# All-in-one_Starter_Kit_for_Pico_2V_1_0_1.net
KiCad netlist of a schematic drawn in EAGLE
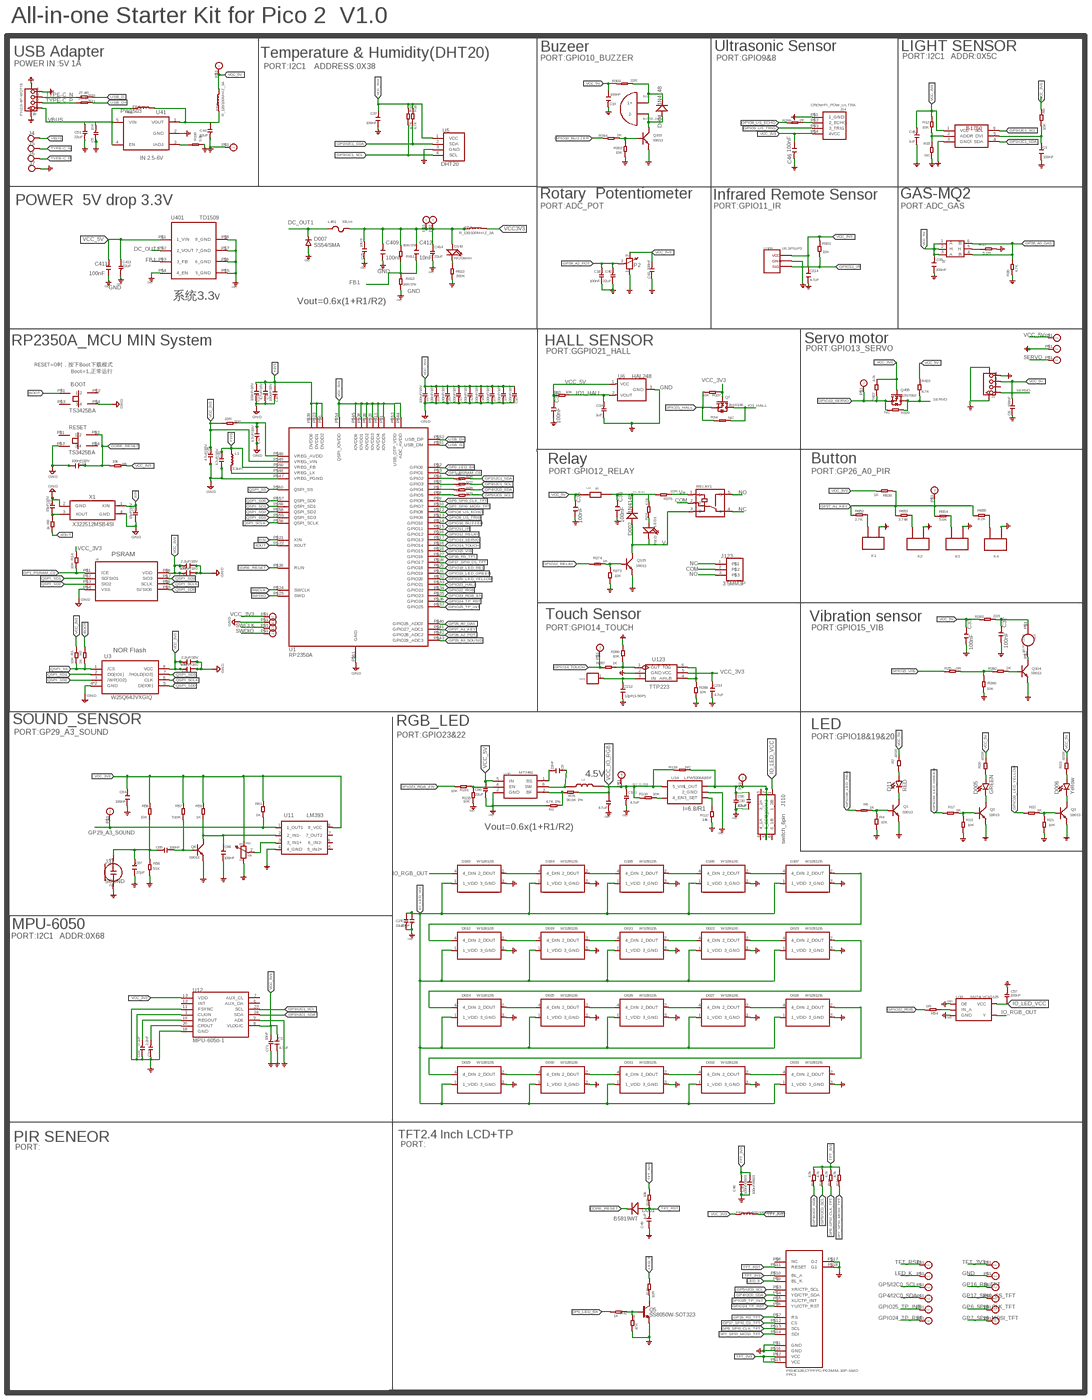
[diagram p0: schematic, sheet 1, overview]
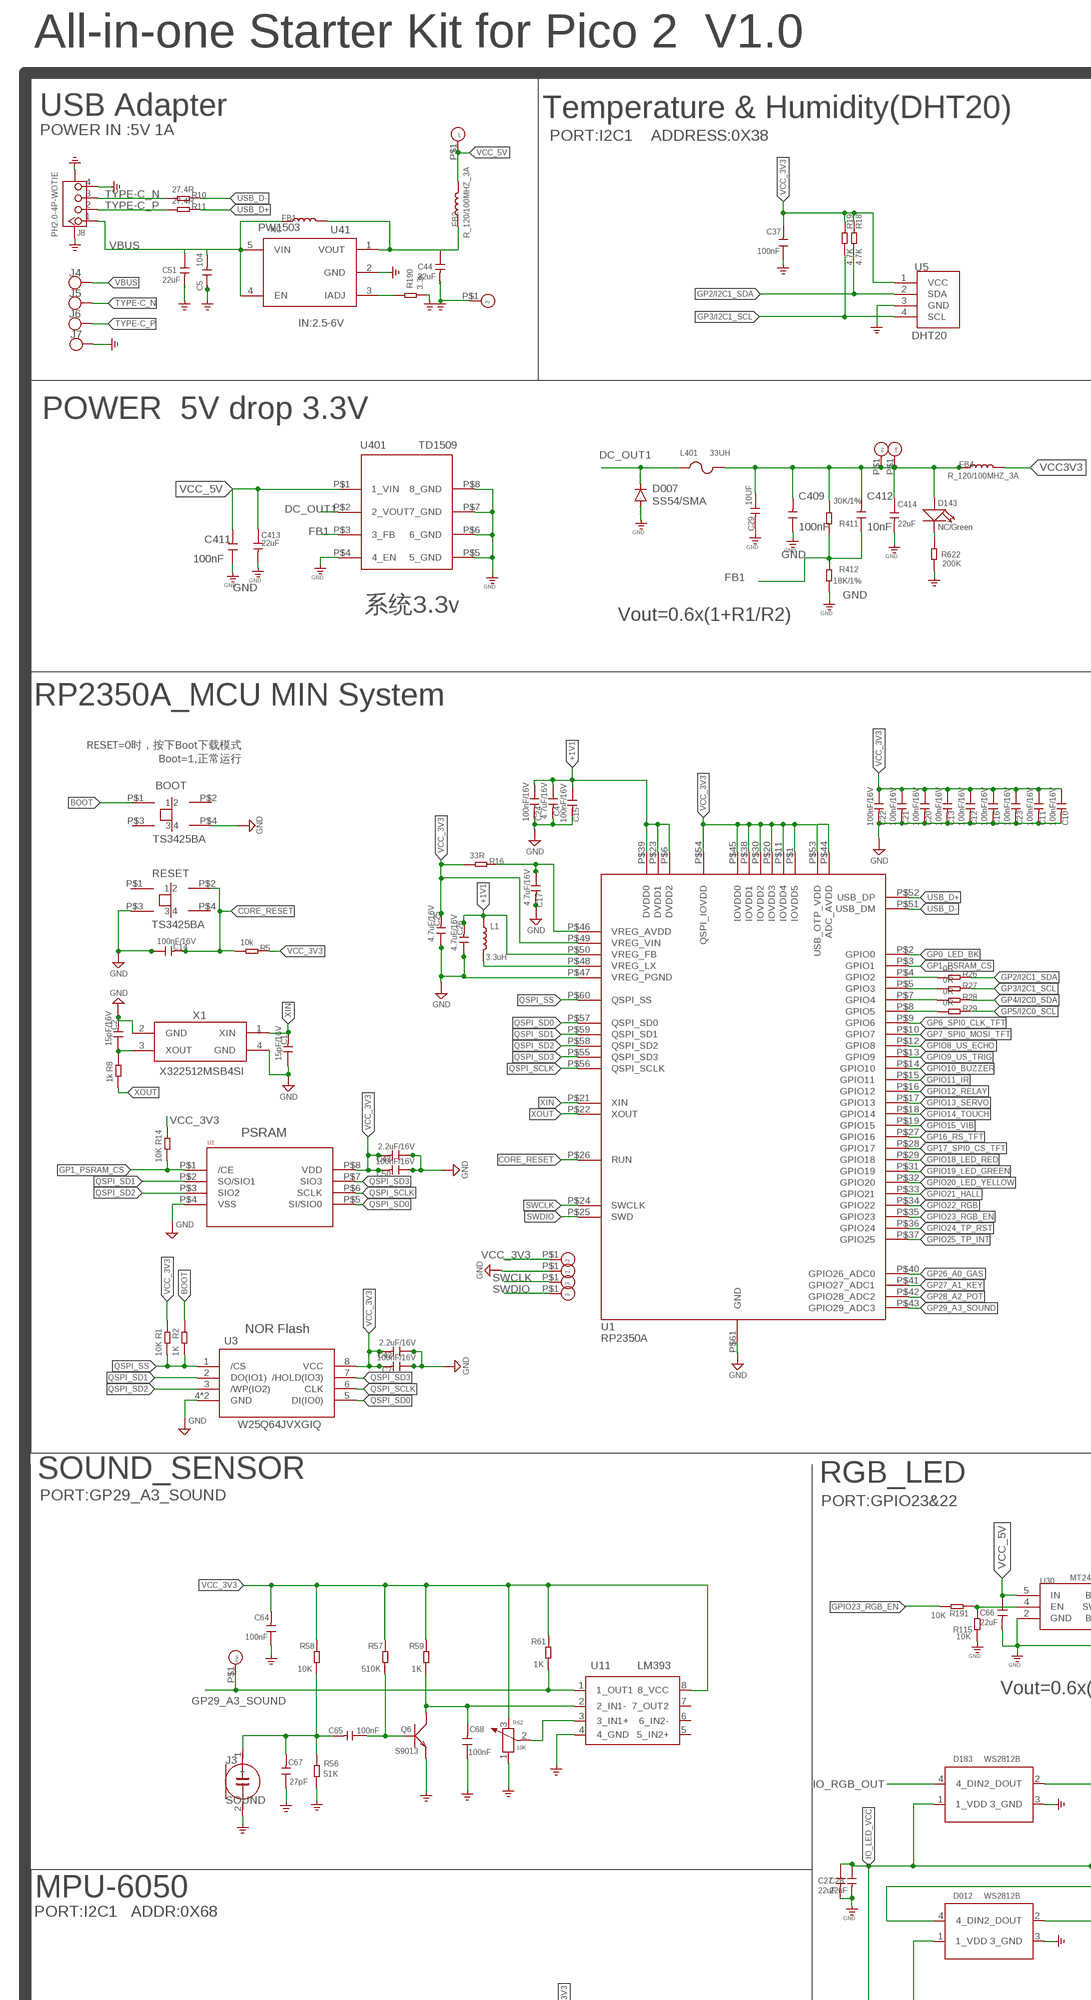
[diagram p1: schematic, sheet 1, part 1 of 4]
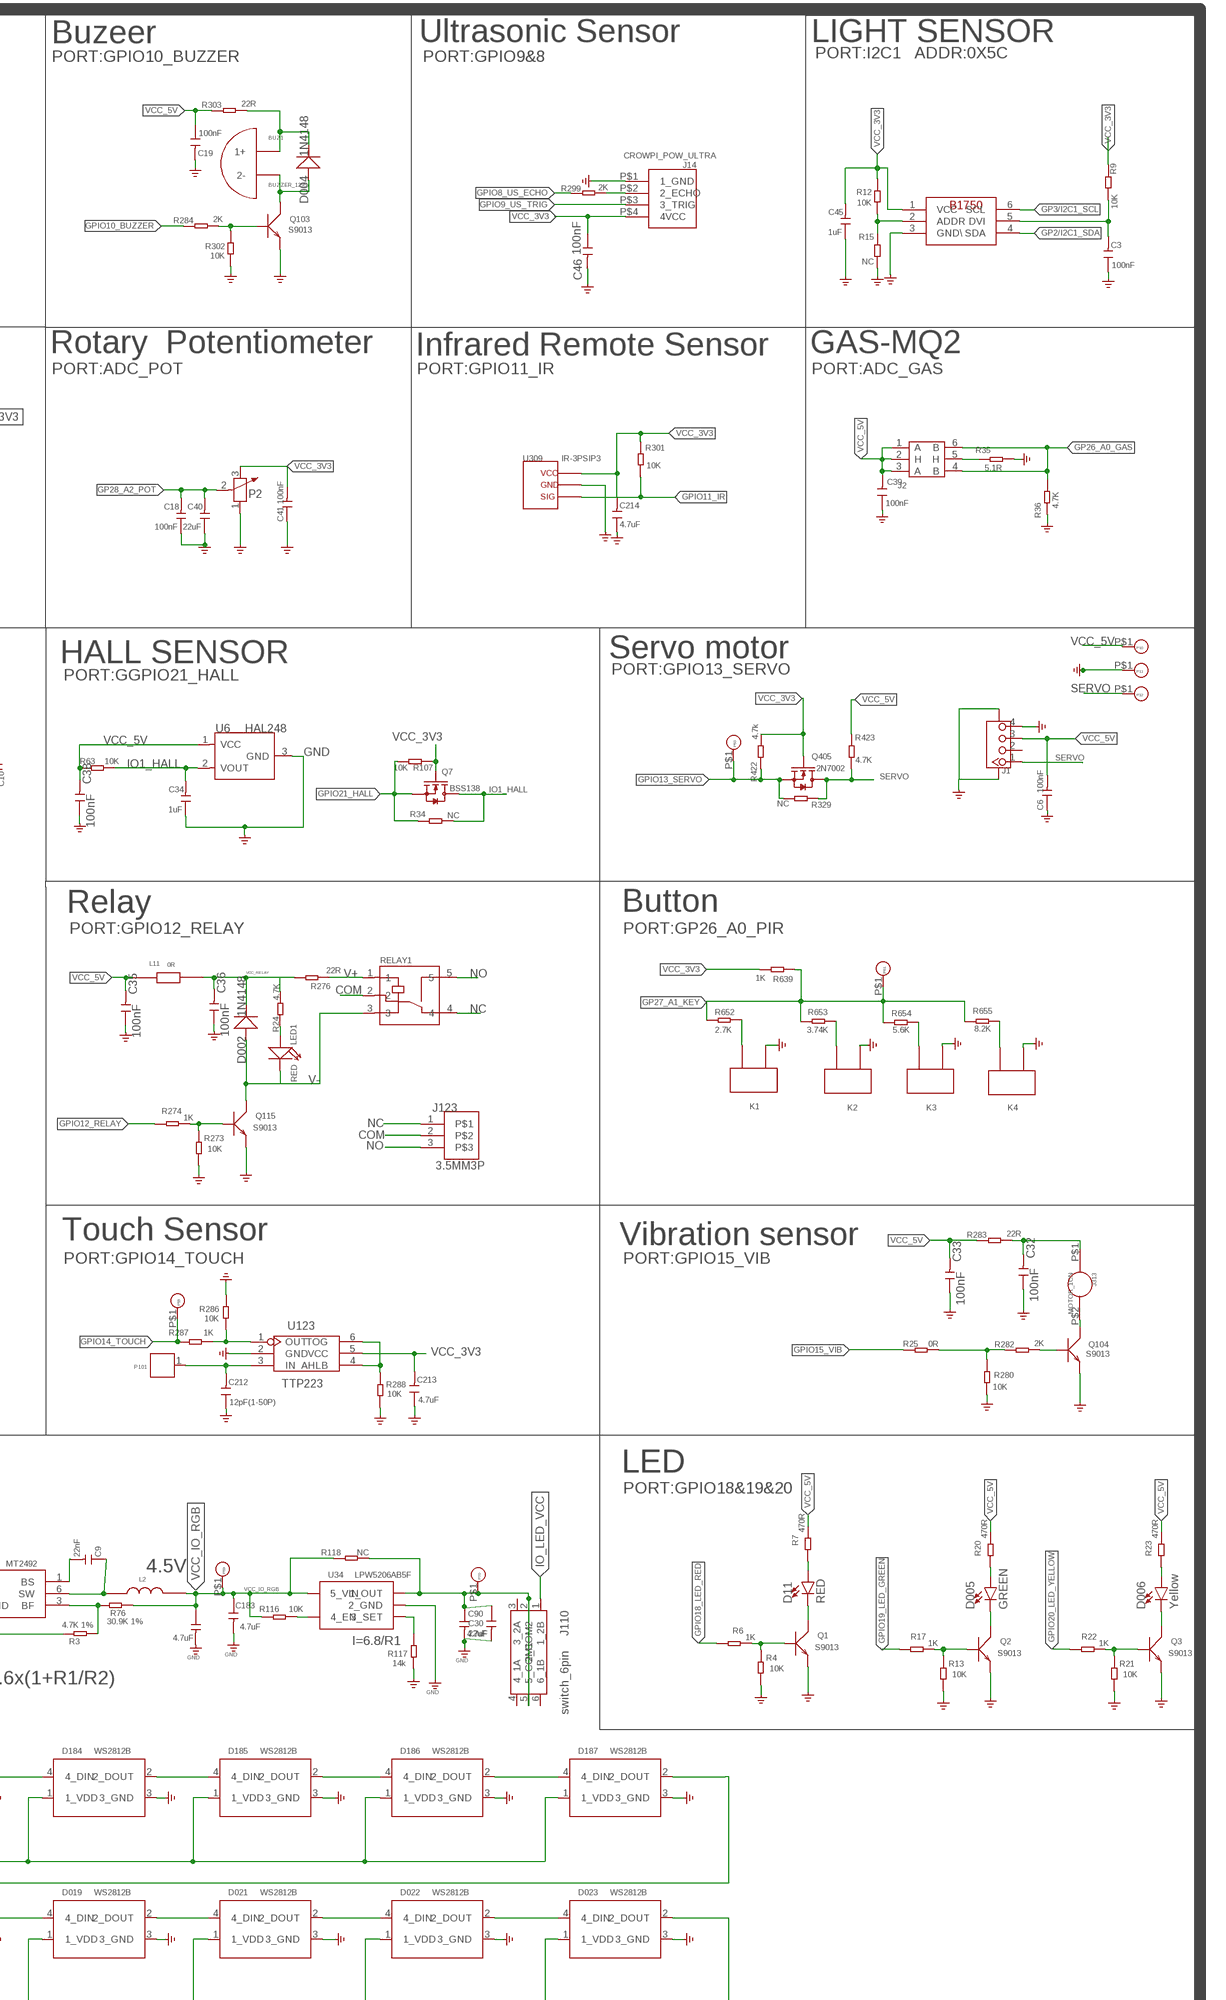
[diagram p2: schematic, sheet 1, part 2 of 4]
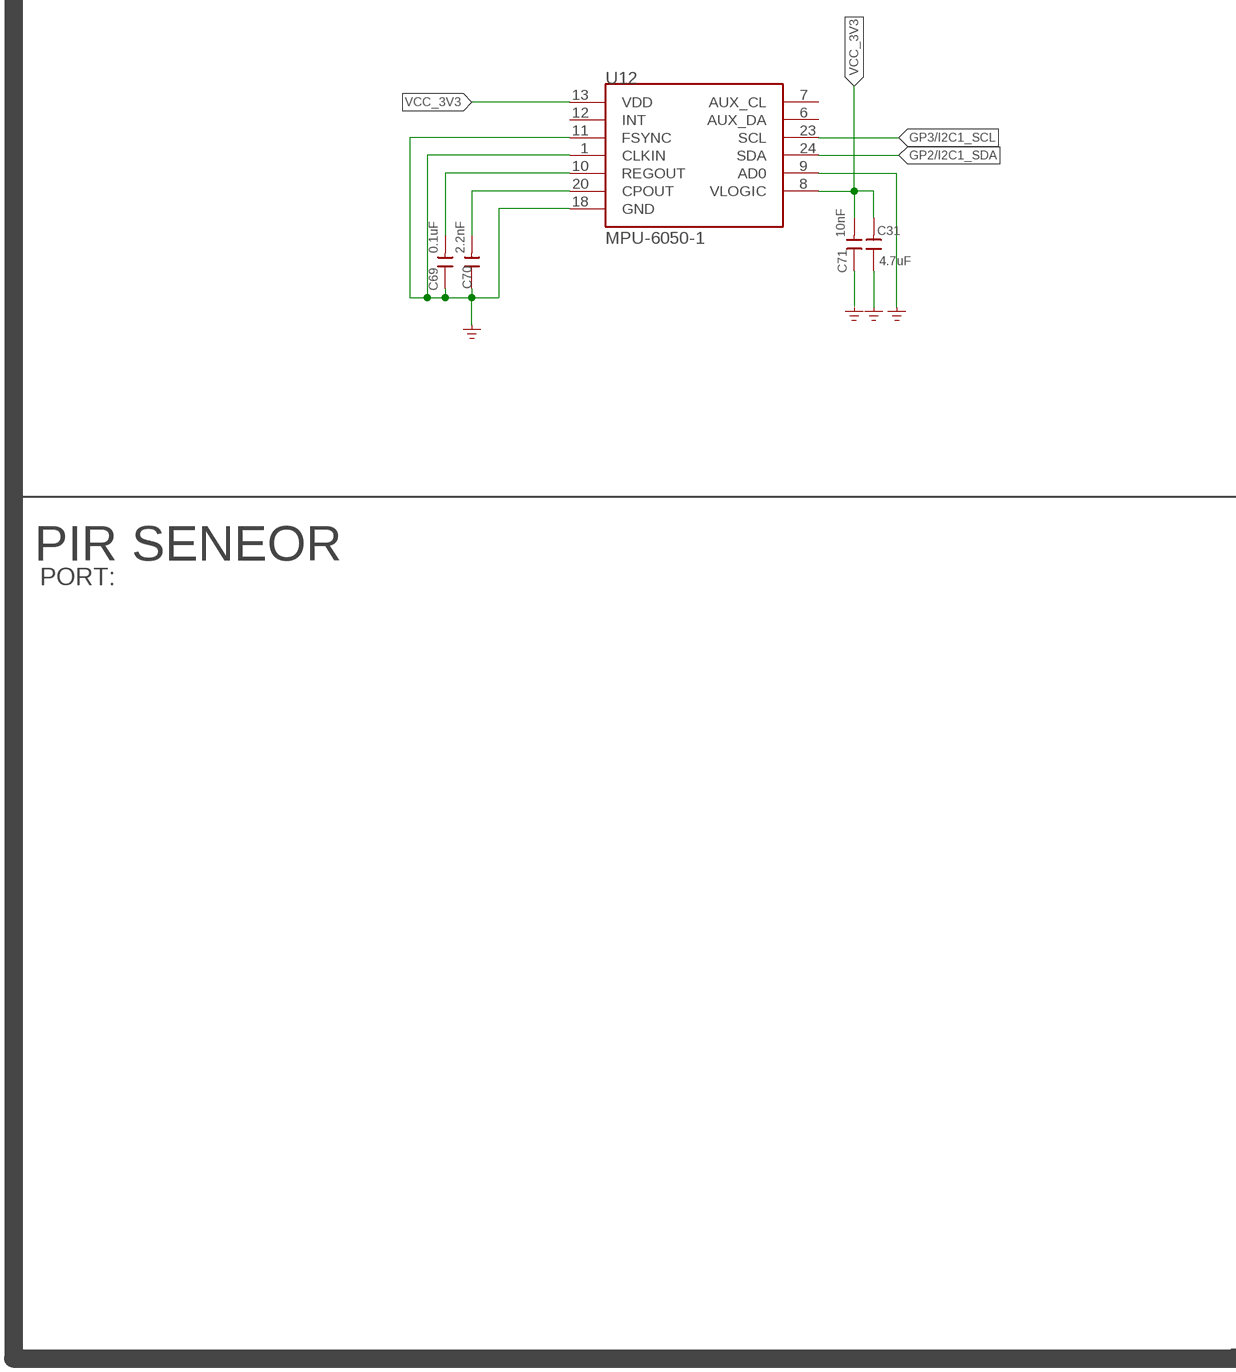
[diagram p3: schematic, sheet 1, part 3 of 4]
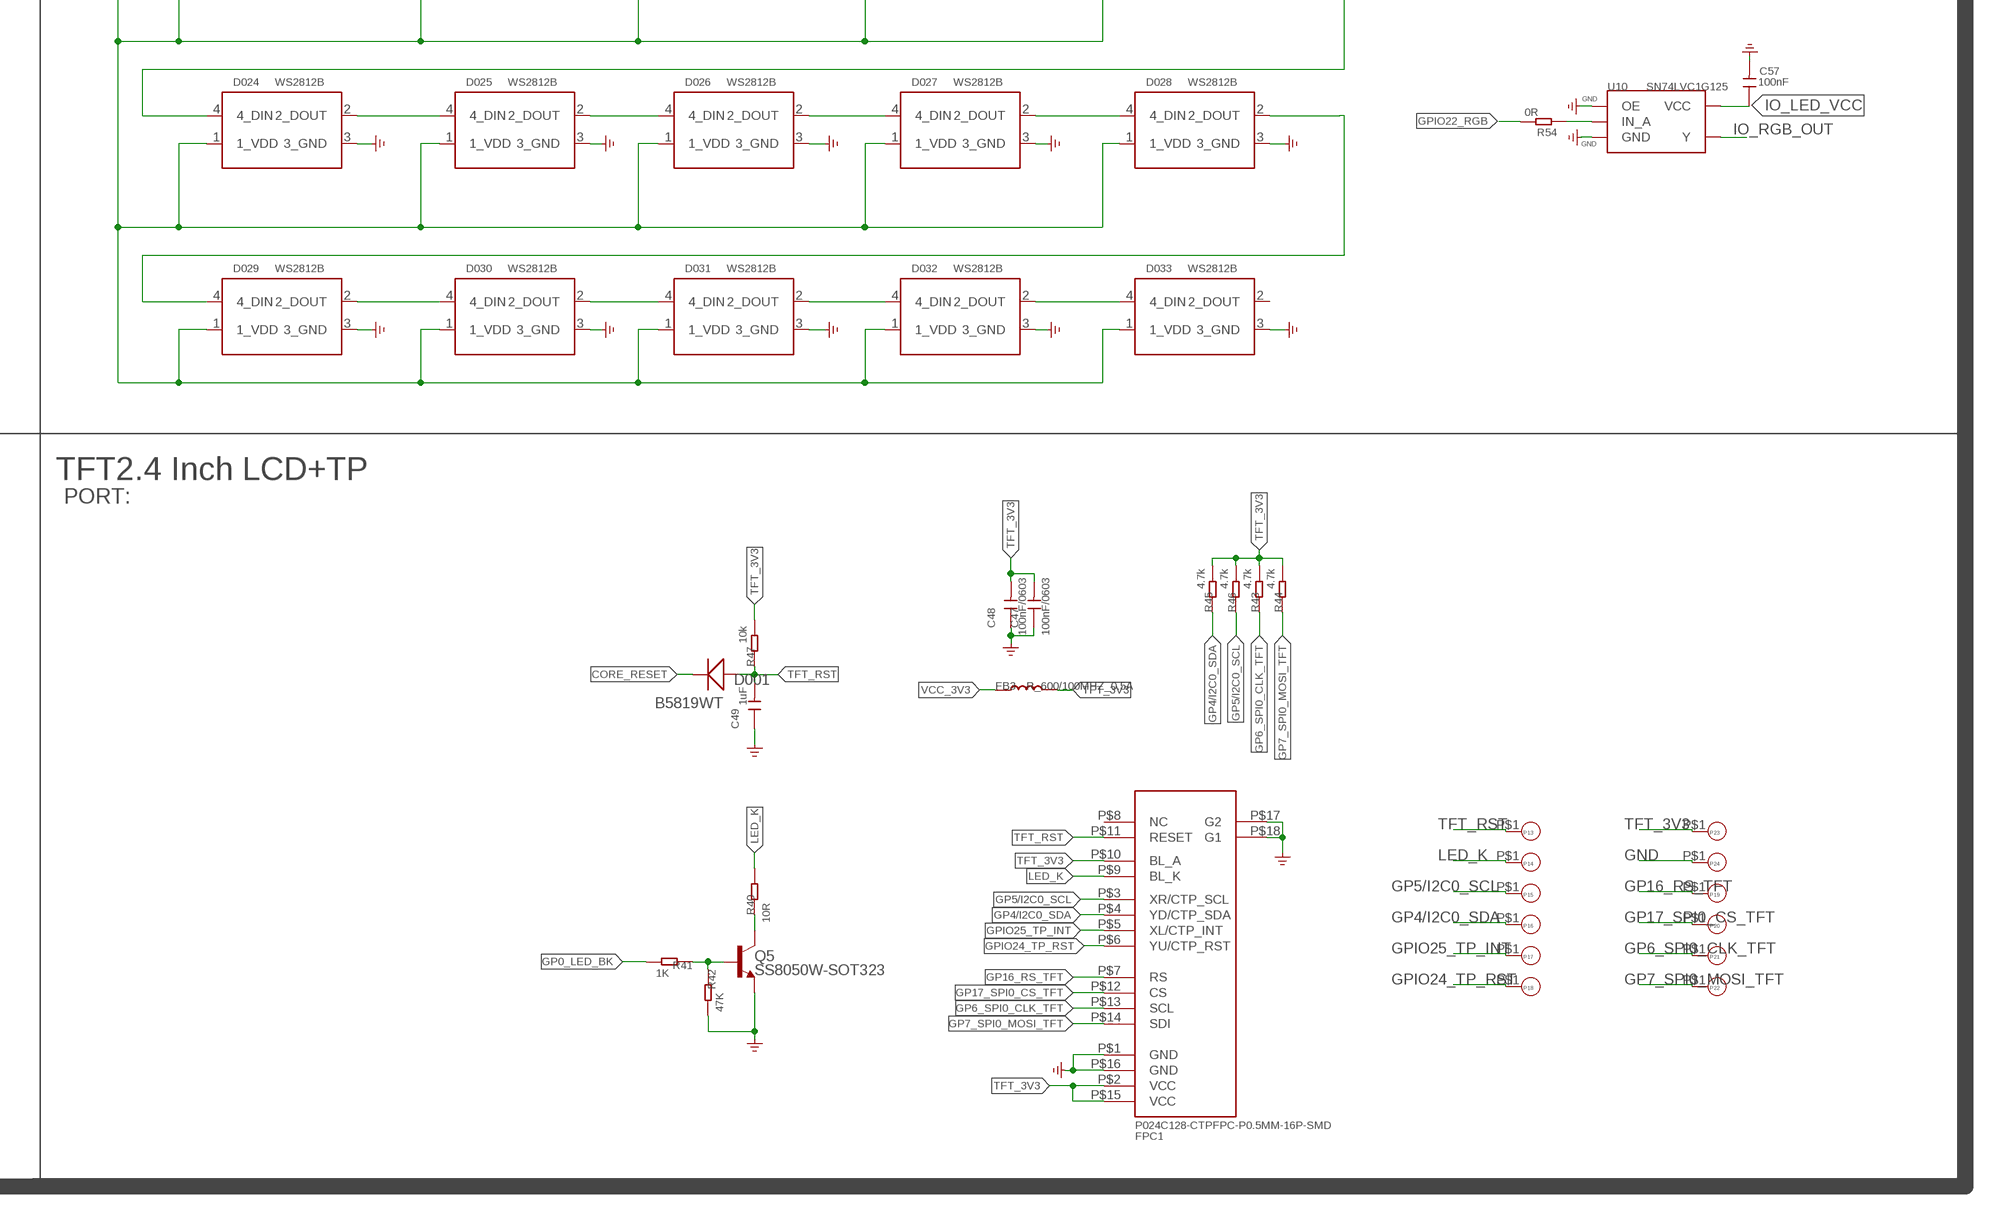
[diagram p4: schematic, sheet 1, part 4 of 4]

(export (version "E")
  (design (tool "Eeschema 10.0.6"))
  (components
    (comp (ref "BOOT")
      (value "TS3425BA")
      (footprint "eagle-import:SMD_KEY4.2_3._.2.5")
      (libsource (lib "eagle-import") (part "KEY"))
    )
    (comp (ref "BUZ1")
      (value "BUZZER_1295")
      (footprint "eagle-import:BUZZER-D12MM-DIP2")
      (libsource (lib "eagle-import") (part "BUZZERBUZZER_1295_DIP"))
    )
    (comp (ref "C1")
      (value "15pF/16V")
      (footprint "eagle-import:C0603")
      (libsource (lib "eagle-import") (part "CAPC0603"))
    )
    (comp (ref "C2")
      (value "15pF/16V")
      (footprint "eagle-import:C0603")
      (libsource (lib "eagle-import") (part "CAPC0603"))
    )
    (comp (ref "C3")
      (value "100nF")
      (footprint "eagle-import:C0603")
      (libsource (lib "eagle-import") (part "CAPC0603"))
    )
    (comp (ref "C4")
      (value "4.7uF/16V")
      (footprint "eagle-import:C0603")
      (libsource (lib "eagle-import") (part "CAPC0603"))
    )
    (comp (ref "C5")
      (value "104")
      (footprint "eagle-import:C0805")
      (libsource (lib "eagle-import") (part "CAPC0805"))
    )
    (comp (ref "C6")
      (value "100nF")
      (footprint "eagle-import:C0603")
      (libsource (lib "eagle-import") (part "CAPC0603"))
    )
    (comp (ref "C7")
      (value "100nF/16V")
      (footprint "eagle-import:C0603")
      (libsource (lib "eagle-import") (part "CAPC0603"))
    )
    (comp (ref "C8")
      (value "4.7uF")
      (footprint "eagle-import:C0603")
      (libsource (lib "eagle-import") (part "CAPC0603"))
    )
    (comp (ref "C9")
      (value "22nF")
      (footprint "eagle-import:C0603")
      (libsource (lib "eagle-import") (part "CAPC0603"))
    )
    (comp (ref "C10")
      (value "100nF/16V")
      (footprint "eagle-import:C0603")
      (libsource (lib "eagle-import") (part "CAPC0603"))
    )
    (comp (ref "C11")
      (value "100nF/16V")
      (footprint "eagle-import:C0603")
      (libsource (lib "eagle-import") (part "CAPC0603"))
    )
    (comp (ref "C12")
      (value "100nF/16V")
      (footprint "eagle-import:C0603")
      (libsource (lib "eagle-import") (part "CAPC0603"))
    )
    (comp (ref "C13")
      (value "100nF/16V")
      (footprint "eagle-import:C0603")
      (libsource (lib "eagle-import") (part "CAPC0603"))
    )
    (comp (ref "C14")
      (value "100nF/16V")
      (footprint "eagle-import:C0603")
      (libsource (lib "eagle-import") (part "CAPC0603"))
    )
    (comp (ref "C15")
      (value "100nF/16V")
      (footprint "eagle-import:C0603")
      (libsource (lib "eagle-import") (part "CAPC0603"))
    )
    (comp (ref "C16")
      (value "100nF/16V")
      (footprint "eagle-import:C0603")
      (libsource (lib "eagle-import") (part "CAPC0603"))
    )
    (comp (ref "C17")
      (value "4.7uF/16V")
      (footprint "eagle-import:C0603")
      (libsource (lib "eagle-import") (part "CAPC0603"))
    )
    (comp (ref "C18")
      (value "100nF")
      (footprint "eagle-import:C0603")
      (libsource (lib "eagle-import") (part "CAPC0603"))
    )
    (comp (ref "C19")
      (value "100nF")
      (footprint "eagle-import:C0603")
      (libsource (lib "eagle-import") (part "CAPC0603"))
    )
    (comp (ref "C20")
      (value "100nF/16V")
      (footprint "eagle-import:C0603")
      (libsource (lib "eagle-import") (part "CAPC0603"))
    )
    (comp (ref "C21")
      (value "100nF/16V")
      (footprint "eagle-import:C0603")
      (libsource (lib "eagle-import") (part "CAPC0603"))
    )
    (comp (ref "C22")
      (value "100nF/16V")
      (footprint "eagle-import:C0603")
      (libsource (lib "eagle-import") (part "CAPC0603"))
    )
    (comp (ref "C23")
      (value "100nF/16V")
      (footprint "eagle-import:C0603")
      (libsource (lib "eagle-import") (part "CAPC0603"))
    )
    (comp (ref "C24")
      (value "100nF/16V")
      (footprint "eagle-import:C0603")
      (libsource (lib "eagle-import") (part "CAPC0603"))
    )
    (comp (ref "C25")
      (value "4.7uF/16V")
      (footprint "eagle-import:C0603")
      (libsource (lib "eagle-import") (part "CAPC0603"))
    )
    (comp (ref "C26")
      (value "4.7uF/16V")
      (footprint "eagle-import:C0603")
      (libsource (lib "eagle-import") (part "CAPC0603"))
    )
    (comp (ref "C27")
      (value "22uF")
      (footprint "eagle-import:C0805")
      (libsource (lib "eagle-import") (part "CAPC0805"))
    )
    (comp (ref "C28")
      (value "22uF")
      (footprint "eagle-import:C0805")
      (libsource (lib "eagle-import") (part "CAPC0805"))
    )
    (comp (ref "C29")
      (value "10UF")
      (footprint "eagle-import:C0805")
      (libsource (lib "eagle-import") (part "CAPC0805"))
    )
    (comp (ref "C30")
      (value "22uF")
      (footprint "eagle-import:C0805")
      (libsource (lib "eagle-import") (part "CAPC0805"))
    )
    (comp (ref "C31")
      (value "4.7uF")
      (footprint "eagle-import:C0603")
      (libsource (lib "eagle-import") (part "CAPC0603"))
    )
    (comp (ref "C32")
      (value "100nF")
      (footprint "eagle-import:C0603")
      (libsource (lib "eagle-import") (part "CAPC0603"))
    )
    (comp (ref "C33")
      (value "100nF")
      (footprint "eagle-import:C0603")
      (libsource (lib "eagle-import") (part "CAPC0603"))
    )
    (comp (ref "C34")
      (value "1uF")
      (footprint "eagle-import:C0603")
      (libsource (lib "eagle-import") (part "CAPC0603"))
    )
    (comp (ref "C35")
      (value "100nF")
      (footprint "eagle-import:C0603")
      (libsource (lib "eagle-import") (part "CAPC0603"))
    )
    (comp (ref "C36")
      (value "100nF")
      (footprint "eagle-import:C0603")
      (libsource (lib "eagle-import") (part "CAPC0603"))
    )
    (comp (ref "C37")
      (value "100nF")
      (footprint "eagle-import:C0603")
      (libsource (lib "eagle-import") (part "CAPC0603"))
    )
    (comp (ref "C38")
      (value "100nF")
      (footprint "eagle-import:C0603")
      (libsource (lib "eagle-import") (part "CAPC0603"))
    )
    (comp (ref "C39")
      (value "100nF")
      (footprint "eagle-import:C0603")
      (libsource (lib "eagle-import") (part "CAPC0603"))
    )
    (comp (ref "C40")
      (value "22uF")
      (footprint "eagle-import:C0603")
      (libsource (lib "eagle-import") (part "CAPC0603"))
    )
    (comp (ref "C41")
      (value "100nF")
      (footprint "eagle-import:C0603")
      (libsource (lib "eagle-import") (part "CAPC0603"))
    )
    (comp (ref "C42")
      (value "2.2uF/16V")
      (footprint "eagle-import:C0603")
      (libsource (lib "eagle-import") (part "CAPC0603"))
    )
    (comp (ref "C43")
      (value "2.2uF/16V")
      (footprint "eagle-import:C0603")
      (libsource (lib "eagle-import") (part "CAPC0603"))
    )
    (comp (ref "C44")
      (value "22uF")
      (footprint "eagle-import:C0805")
      (libsource (lib "eagle-import") (part "CAPC0805"))
    )
    (comp (ref "C45")
      (value "1uF")
      (footprint "eagle-import:C0603")
      (libsource (lib "eagle-import") (part "CAPC0603"))
    )
    (comp (ref "C46")
      (value "100nF")
      (footprint "eagle-import:C0603")
      (libsource (lib "eagle-import") (part "CAPC0603"))
    )
    (comp (ref "C47")
      (value "100nF/0603")
      (footprint "eagle-import:C0603")
      (libsource (lib "eagle-import") (part "CAPC0603"))
    )
    (comp (ref "C48")
      (value "100nF/0603")
      (footprint "eagle-import:C0603")
      (libsource (lib "eagle-import") (part "CAPC0603"))
    )
    (comp (ref "C49")
      (value "1uF")
      (footprint "eagle-import:C0603")
      (libsource (lib "eagle-import") (part "CAPC0603"))
    )
    (comp (ref "C50")
      (value "100nF/16V")
      (footprint "eagle-import:C0603")
      (libsource (lib "eagle-import") (part "CAPC0603"))
    )
    (comp (ref "C51")
      (value "22uF")
      (footprint "eagle-import:C0805")
      (libsource (lib "eagle-import") (part "CAPC0805"))
    )
    (comp (ref "C57")
      (value "100nF")
      (footprint "eagle-import:C0603")
      (libsource (lib "eagle-import") (part "CAPC0603"))
    )
    (comp (ref "C64")
      (value "100nF")
      (footprint "eagle-import:C0603")
      (libsource (lib "eagle-import") (part "CAPC0603"))
    )
    (comp (ref "C65")
      (value "100nF")
      (footprint "eagle-import:C0603")
      (libsource (lib "eagle-import") (part "CAPC0603"))
    )
    (comp (ref "C66")
      (value "22uF")
      (footprint "eagle-import:C0805")
      (libsource (lib "eagle-import") (part "CAPC0805"))
    )
    (comp (ref "C67")
      (value "27pF")
      (footprint "eagle-import:C0603")
      (libsource (lib "eagle-import") (part "CAPC0603"))
    )
    (comp (ref "C68")
      (value "100nF")
      (footprint "eagle-import:C0603")
      (libsource (lib "eagle-import") (part "CAPC0603"))
    )
    (comp (ref "C69")
      (value "0.1uF")
      (footprint "eagle-import:C0603")
      (libsource (lib "eagle-import") (part "CAPC0603"))
    )
    (comp (ref "C70")
      (value "2.2nF")
      (footprint "eagle-import:C0603")
      (libsource (lib "eagle-import") (part "CAPC0603"))
    )
    (comp (ref "C71")
      (value "10nF")
      (footprint "eagle-import:C0603")
      (libsource (lib "eagle-import") (part "CAPC0603"))
    )
    (comp (ref "C90")
      (value "4.7uF")
      (footprint "eagle-import:C0603")
      (libsource (lib "eagle-import") (part "CAPC0603"))
    )
    (comp (ref "C183")
      (value "4.7uF")
      (footprint "eagle-import:C0603")
      (libsource (lib "eagle-import") (part "CAPC0603"))
    )
    (comp (ref "C212")
      (value "12pF(1-50P)")
      (footprint "eagle-import:C0603")
      (libsource (lib "eagle-import") (part "CAPC0603"))
    )
    (comp (ref "C213")
      (value "4.7uF")
      (footprint "eagle-import:C0603")
      (libsource (lib "eagle-import") (part "CAPC0603"))
    )
    (comp (ref "C214")
      (value "4.7uF")
      (footprint "eagle-import:C0603")
      (libsource (lib "eagle-import") (part "CAPC0603"))
    )
    (comp (ref "C409")
      (value "100nF")
      (footprint "eagle-import:C0603")
      (libsource (lib "eagle-import") (part "CAPC0603"))
    )
    (comp (ref "C411")
      (value "100nF")
      (footprint "eagle-import:C0603")
      (libsource (lib "eagle-import") (part "CAPC0603"))
    )
    (comp (ref "C412")
      (value "10nF")
      (footprint "eagle-import:C0603")
      (libsource (lib "eagle-import") (part "CAPC0603"))
    )
    (comp (ref "C413")
      (value "22uF")
      (footprint "eagle-import:C0805")
      (libsource (lib "eagle-import") (part "CAPC0805"))
    )
    (comp (ref "C414")
      (value "22uF")
      (footprint "eagle-import:C0805")
      (libsource (lib "eagle-import") (part "CAPC0805"))
    )
    (comp (ref "D001")
      (value "B5819WT")
      (footprint "eagle-import:D_SOD523")
      (libsource (lib "eagle-import") (part "DIODE0603"))
    )
    (comp (ref "D002")
      (value "1N4148")
      (footprint "eagle-import:D_SOD123")
      (libsource (lib "eagle-import") (part "Crowtail_Starter_DIODE1206"))
    )
    (comp (ref "D004")
      (value "1N4148")
      (footprint "eagle-import:D_SOD123")
      (libsource (lib "eagle-import") (part "Crowtail_Starter_DIODE1206"))
    )
    (comp (ref "D005")
      (value "GREEN")
      (footprint "eagle-import:LED-8MM")
      (libsource (lib "eagle-import") (part "LED"))
    )
    (comp (ref "D006")
      (value "Yellow")
      (footprint "eagle-import:LED-8MM")
      (libsource (lib "eagle-import") (part "LED"))
    )
    (comp (ref "D007")
      (value "SS54/SMA")
      (footprint "eagle-import:DIODE_DO-214AC")
      (libsource (lib "eagle-import") (part "DIODE_DIODE-DO-214AC"))
    )
    (comp (ref "D11")
      (value "RED")
      (footprint "eagle-import:LED-8MM")
      (libsource (lib "eagle-import") (part "LED"))
    )
    (comp (ref "D012")
      (value "WS2812B")
      (footprint "eagle-import:LED_RGB_WS2812_3535")
      (libsource (lib "eagle-import") (part "LED_RGB_WS2812_3535"))
    )
    (comp (ref "D019")
      (value "WS2812B")
      (footprint "eagle-import:LED_RGB_WS2812_3535")
      (libsource (lib "eagle-import") (part "LED_RGB_WS2812_3535"))
    )
    (comp (ref "D021")
      (value "WS2812B")
      (footprint "eagle-import:LED_RGB_WS2812_3535")
      (libsource (lib "eagle-import") (part "LED_RGB_WS2812_3535"))
    )
    (comp (ref "D022")
      (value "WS2812B")
      (footprint "eagle-import:LED_RGB_WS2812_3535")
      (libsource (lib "eagle-import") (part "LED_RGB_WS2812_3535"))
    )
    (comp (ref "D023")
      (value "WS2812B")
      (footprint "eagle-import:LED_RGB_WS2812_3535")
      (libsource (lib "eagle-import") (part "LED_RGB_WS2812_3535"))
    )
    (comp (ref "D024")
      (value "WS2812B")
      (footprint "eagle-import:LED_RGB_WS2812_3535")
      (libsource (lib "eagle-import") (part "LED_RGB_WS2812_3535"))
    )
    (comp (ref "D025")
      (value "WS2812B")
      (footprint "eagle-import:LED_RGB_WS2812_3535")
      (libsource (lib "eagle-import") (part "LED_RGB_WS2812_3535"))
    )
    (comp (ref "D026")
      (value "WS2812B")
      (footprint "eagle-import:LED_RGB_WS2812_3535")
      (libsource (lib "eagle-import") (part "LED_RGB_WS2812_3535"))
    )
    (comp (ref "D027")
      (value "WS2812B")
      (footprint "eagle-import:LED_RGB_WS2812_3535")
      (libsource (lib "eagle-import") (part "LED_RGB_WS2812_3535"))
    )
    (comp (ref "D028")
      (value "WS2812B")
      (footprint "eagle-import:LED_RGB_WS2812_3535")
      (libsource (lib "eagle-import") (part "LED_RGB_WS2812_3535"))
    )
    (comp (ref "D029")
      (value "WS2812B")
      (footprint "eagle-import:LED_RGB_WS2812_3535")
      (libsource (lib "eagle-import") (part "LED_RGB_WS2812_3535"))
    )
    (comp (ref "D030")
      (value "WS2812B")
      (footprint "eagle-import:LED_RGB_WS2812_3535")
      (libsource (lib "eagle-import") (part "LED_RGB_WS2812_3535"))
    )
    (comp (ref "D031")
      (value "WS2812B")
      (footprint "eagle-import:LED_RGB_WS2812_3535")
      (libsource (lib "eagle-import") (part "LED_RGB_WS2812_3535"))
    )
    (comp (ref "D032")
      (value "WS2812B")
      (footprint "eagle-import:LED_RGB_WS2812_3535")
      (libsource (lib "eagle-import") (part "LED_RGB_WS2812_3535"))
    )
    (comp (ref "D033")
      (value "WS2812B")
      (footprint "eagle-import:LED_RGB_WS2812_3535")
      (libsource (lib "eagle-import") (part "LED_RGB_WS2812_3535"))
    )
    (comp (ref "D143")
      (value "NC/Green")
      (footprint "eagle-import:LED_0603_SMT")
      (libsource (lib "eagle-import") (part "LED_0603_SMT"))
    )
    (comp (ref "D183")
      (value "WS2812B")
      (footprint "eagle-import:LED_RGB_WS2812_3535")
      (libsource (lib "eagle-import") (part "LED_RGB_WS2812_3535"))
    )
    (comp (ref "D184")
      (value "WS2812B")
      (footprint "eagle-import:LED_RGB_WS2812_3535")
      (libsource (lib "eagle-import") (part "LED_RGB_WS2812_3535"))
    )
    (comp (ref "D185")
      (value "WS2812B")
      (footprint "eagle-import:LED_RGB_WS2812_3535")
      (libsource (lib "eagle-import") (part "LED_RGB_WS2812_3535"))
    )
    (comp (ref "D186")
      (value "WS2812B")
      (footprint "eagle-import:LED_RGB_WS2812_3535")
      (libsource (lib "eagle-import") (part "LED_RGB_WS2812_3535"))
    )
    (comp (ref "D187")
      (value "WS2812B")
      (footprint "eagle-import:LED_RGB_WS2812_3535")
      (libsource (lib "eagle-import") (part "LED_RGB_WS2812_3535"))
    )
    (comp (ref "FB1")
      (value "NC")
      (footprint "eagle-import:L0805")
      (libsource (lib "eagle-import") (part "R_120/100MHZ_3A"))
    )
    (comp (ref "FB2")
      (value "R_120/100MHZ_3A")
      (footprint "eagle-import:L0805")
      (libsource (lib "eagle-import") (part "R_120/100MHZ_3A"))
    )
    (comp (ref "FB3")
      (value "R_600/100MHZ_0.5A")
      (footprint "eagle-import:L0603")
      (libsource (lib "eagle-import") (part "R_600/100MHZ_0.5A"))
    )
    (comp (ref "FB4")
      (value "R_120/100MHZ_3A")
      (footprint "eagle-import:L0805")
      (libsource (lib "eagle-import") (part "R_120/100MHZ_3A"))
    )
    (comp (ref "FPC1")
      (value "P024C128-CTPFPC-P0.5MM-16P-SMD")
      (footprint "eagle-import:FPC-P0.5MM-16P-SMD")
      (libsource (lib "eagle-import") (part "P024C128-CTPFPC-P0.5MM-16P-SMD"))
    )
    (comp (ref "J1")
      (value "A_XBJ_CONNECTOR_TWIG-4P-2.0-SMD-FEMALE-REINFORCE90D")
      (footprint "eagle-import:A_XBJ_CONNECTOR_4P-SMD-2.0-90D")
      (libsource (lib "eagle-import") (part "A_XBJ_CONNECTOR_TWIG-4P-2.0-SMD-FEMALE-REINFORCE90D"))
    )
    (comp (ref "J2")
      (value "MQ-SOCKET")
      (footprint "eagle-import:MQ2")
      (libsource (lib "eagle-import") (part "MQ-SOCKET"))
    )
    (comp (ref "J3")
      (value "SOUND")
      (footprint "eagle-import:TEMPLATE_2P-D8.9MM")
      (libsource (lib "eagle-import") (part "TEMPLATE_MICROPHONE"))
    )
    (comp (ref "J4")
      (value "TP-SMDTP-SMD-2X4MM")
      (footprint "eagle-import:TP-SMD-2X4MM")
      (libsource (lib "eagle-import") (part "TP-SMDTP-SMD-2X4MM"))
    )
    (comp (ref "J5")
      (value "TP-SMDTP-SMD-2X4MM")
      (footprint "eagle-import:TP-SMD-2X4MM")
      (libsource (lib "eagle-import") (part "TP-SMDTP-SMD-2X4MM"))
    )
    (comp (ref "J6")
      (value "TP-SMDTP-SMD-2X4MM")
      (footprint "eagle-import:TP-SMD-2X4MM")
      (libsource (lib "eagle-import") (part "TP-SMDTP-SMD-2X4MM"))
    )
    (comp (ref "J7")
      (value "TP-SMDTP-SMD-2X4MM")
      (footprint "eagle-import:TP-SMD-2X4MM")
      (libsource (lib "eagle-import") (part "TP-SMDTP-SMD-2X4MM"))
    )
    (comp (ref "J8")
      (value "PH2.0-4P-WOTIE")
      (footprint "eagle-import:PH2.0-4P")
      (libsource (lib "eagle-import") (part "PH2.0-4P-WOTIE"))
    )
    (comp (ref "J14")
      (value "CROWPI_POW_ULTRA")
      (footprint "eagle-import:CROWPI_POW_ULTRA")
      (libsource (lib "eagle-import") (part "CROWPI_POW_ULTRA"))
    )
    (comp (ref "J110")
      (value "switch_6pin")
      (footprint "eagle-import:SWITCH_6PIN_2P")
      (libsource (lib "eagle-import") (part "SWITCH_6PIN_2P"))
    )
    (comp (ref "J123")
      (value "3.5MM3P")
      (footprint "eagle-import:3.5MM_3P")
      (libsource (lib "eagle-import") (part "3.5MM3P"))
    )
    (comp (ref "J313")
      (value "MOTOR_1CN")
      (footprint "eagle-import:MOTOR_1CM")
      (libsource (lib "eagle-import") (part "MOTOR_1CN"))
    )
    (comp (ref "K1")
      (value "BUTTON_2P")
      (footprint "eagle-import:BUTTON_2P")
      (libsource (lib "eagle-import") (part "BUTTON_2P"))
    )
    (comp (ref "K2")
      (value "BUTTON_2P")
      (footprint "eagle-import:BUTTON_2P")
      (libsource (lib "eagle-import") (part "BUTTON_2P"))
    )
    (comp (ref "K3")
      (value "BUTTON_2P")
      (footprint "eagle-import:BUTTON_2P")
      (libsource (lib "eagle-import") (part "BUTTON_2P"))
    )
    (comp (ref "K4")
      (value "BUTTON_2P")
      (footprint "eagle-import:BUTTON_2P")
      (libsource (lib "eagle-import") (part "BUTTON_2P"))
    )
    (comp (ref "L1")
      (value "3.3uH")
      (footprint "eagle-import:SMD,1.6X2MM")
      (libsource (lib "eagle-import") (part "FTC201610S3R3MBCA"))
    )
    (comp (ref "L2")
      (value "CD32_950MA")
      (footprint "eagle-import:CD32")
      (libsource (lib "eagle-import") (part "CD32_950MA"))
    )
    (comp (ref "L11")
      (value "0R")
      (footprint "eagle-import:201209")
      (libsource (lib "eagle-import") (part "CMP201209UD1R0MT201209"))
    )
    (comp (ref "L401")
      (value "33UH")
      (footprint "eagle-import:L773")
      (libsource (lib "eagle-import") (part "L-773"))
    )
    (comp (ref "LED1")
      (value "RED")
      (footprint "eagle-import:DISCRETE_LED-0603")
      (libsource (lib "eagle-import") (part "DISCRETE_LED0603"))
    )
    (comp (ref "P1")
      (value "PADPAD-1.0MM")
      (footprint "eagle-import:PAD-1.0MM")
      (libsource (lib "eagle-import") (part "PADPAD-1.0MM"))
    )
    (comp (ref "P2")
      (value "R-POTENTIOMETER")
      (footprint "eagle-import:3P-SQUA-45.6X10X5.8H")
      (libsource (lib "eagle-import") (part "R-POTENTIOMETER"))
    )
    (comp (ref "P3")
      (value "PADPAD-1.0MM")
      (footprint "eagle-import:PAD-1.0MM")
      (libsource (lib "eagle-import") (part "PADPAD-1.0MM"))
    )
    (comp (ref "P4")
      (value "PADPAD-1.0MM")
      (footprint "eagle-import:PAD-1.0MM")
      (libsource (lib "eagle-import") (part "PADPAD-1.0MM"))
    )
    (comp (ref "P5")
      (value "PADPAD-1.0MM")
      (footprint "eagle-import:PAD-1.0MM")
      (libsource (lib "eagle-import") (part "PADPAD-1.0MM"))
    )
    (comp (ref "P6")
      (value "PADPAD-1.0MM")
      (footprint "eagle-import:PAD-1.0MM")
      (libsource (lib "eagle-import") (part "PADPAD-1.0MM"))
    )
    (comp (ref "P7")
      (value "PADPAD-1.0MM")
      (footprint "eagle-import:PAD-1.0MM")
      (libsource (lib "eagle-import") (part "PADPAD-1.0MM"))
    )
    (comp (ref "P8")
      (value "PADPAD-1.0MM")
      (footprint "eagle-import:PAD-1.0MM")
      (libsource (lib "eagle-import") (part "PADPAD-1.0MM"))
    )
    (comp (ref "P9")
      (value "PADPAD-1.0MM")
      (footprint "eagle-import:PAD-1.0MM")
      (libsource (lib "eagle-import") (part "PADPAD-1.0MM"))
    )
    (comp (ref "P10")
      (value "PADPAD-1.0MM")
      (footprint "eagle-import:PAD-1.0MM")
      (libsource (lib "eagle-import") (part "PADPAD-1.0MM"))
    )
    (comp (ref "P11")
      (value "PADPAD-1.0MM")
      (footprint "eagle-import:PAD-1.0MM")
      (libsource (lib "eagle-import") (part "PADPAD-1.0MM"))
    )
    (comp (ref "P12")
      (value "PADPAD-1.0MM")
      (footprint "eagle-import:PAD-1.0MM")
      (libsource (lib "eagle-import") (part "PADPAD-1.0MM"))
    )
    (comp (ref "P13")
      (value "PADPAD-1.0MM")
      (footprint "eagle-import:PAD-1.0MM")
      (libsource (lib "eagle-import") (part "PADPAD-1.0MM"))
    )
    (comp (ref "P14")
      (value "PADPAD-1.0MM")
      (footprint "eagle-import:PAD-1.0MM")
      (libsource (lib "eagle-import") (part "PADPAD-1.0MM"))
    )
    (comp (ref "P15")
      (value "PADPAD-1.0MM")
      (footprint "eagle-import:PAD-1.0MM")
      (libsource (lib "eagle-import") (part "PADPAD-1.0MM"))
    )
    (comp (ref "P16")
      (value "PADPAD-1.0MM")
      (footprint "eagle-import:PAD-1.0MM")
      (libsource (lib "eagle-import") (part "PADPAD-1.0MM"))
    )
    (comp (ref "P17")
      (value "PADPAD-1.0MM")
      (footprint "eagle-import:PAD-1.0MM")
      (libsource (lib "eagle-import") (part "PADPAD-1.0MM"))
    )
    (comp (ref "P18")
      (value "PADPAD-1.0MM")
      (footprint "eagle-import:PAD-1.0MM")
      (libsource (lib "eagle-import") (part "PADPAD-1.0MM"))
    )
    (comp (ref "P19")
      (value "PADPAD-1.0MM")
      (footprint "eagle-import:PAD-1.0MM")
      (libsource (lib "eagle-import") (part "PADPAD-1.0MM"))
    )
    (comp (ref "P20")
      (value "PADPAD-1.0MM")
      (footprint "eagle-import:PAD-1.0MM")
      (libsource (lib "eagle-import") (part "PADPAD-1.0MM"))
    )
    (comp (ref "P21")
      (value "PADPAD-1.0MM")
      (footprint "eagle-import:PAD-1.0MM")
      (libsource (lib "eagle-import") (part "PADPAD-1.0MM"))
    )
    (comp (ref "P22")
      (value "PADPAD-1.0MM")
      (footprint "eagle-import:PAD-1.0MM")
      (libsource (lib "eagle-import") (part "PADPAD-1.0MM"))
    )
    (comp (ref "P23")
      (value "PADPAD-1.0MM")
      (footprint "eagle-import:PAD-1.0MM")
      (libsource (lib "eagle-import") (part "PADPAD-1.0MM"))
    )
    (comp (ref "P24")
      (value "PADPAD-1.0MM")
      (footprint "eagle-import:PAD-1.0MM")
      (libsource (lib "eagle-import") (part "PADPAD-1.0MM"))
    )
    (comp (ref "P30")
      (value "PADPAD-1.0MM")
      (footprint "eagle-import:PAD-1.0MM")
      (libsource (lib "eagle-import") (part "PADPAD-1.0MM"))
    )
    (comp (ref "P53")
      (value "PADPAD-1.0MM")
      (footprint "eagle-import:PAD-1.0MM")
      (libsource (lib "eagle-import") (part "PADPAD-1.0MM"))
    )
    (comp (ref "P55")
      (value "PADPAD-1.0MM")
      (footprint "eagle-import:PAD-1.0MM")
      (libsource (lib "eagle-import") (part "PADPAD-1.0MM"))
    )
    (comp (ref "P61")
      (value "PADPAD-1.0MM")
      (footprint "eagle-import:PAD-1.0MM")
      (libsource (lib "eagle-import") (part "PADPAD-1.0MM"))
    )
    (comp (ref "P69")
      (value "PADPAD-1.0MM")
      (footprint "eagle-import:PAD-1.0MM")
      (libsource (lib "eagle-import") (part "PADPAD-1.0MM"))
    )
    (comp (ref "P70")
      (value "PADPAD-1.0MM")
      (footprint "eagle-import:PAD-1.0MM")
      (libsource (lib "eagle-import") (part "PADPAD-1.0MM"))
    )
    (comp (ref "P101")
      (value "KEY")
      (footprint "eagle-import:1P-D450")
      (libsource (lib "eagle-import") (part "PAD'D450MIL'"))
    )
    (comp (ref "Q1")
      (value "S9013")
      (footprint "eagle-import:SOT23@1")
      (libsource (lib "eagle-import") (part "TRANSISTOR-NPN-SOT23"))
    )
    (comp (ref "Q2")
      (value "S9013")
      (footprint "eagle-import:SOT23@1")
      (libsource (lib "eagle-import") (part "TRANSISTOR-NPN-SOT23"))
    )
    (comp (ref "Q3")
      (value "S9013")
      (footprint "eagle-import:SOT23@1")
      (libsource (lib "eagle-import") (part "TRANSISTOR-NPN-SOT23"))
    )
    (comp (ref "Q5")
      (value "SS8050W-SOT323")
      (footprint "eagle-import:MOS_SOT323")
      (libsource (lib "eagle-import") (part "TRANS_NPN"))
    )
    (comp (ref "Q6")
      (value "S9013")
      (footprint "eagle-import:SOT23@1")
      (libsource (lib "eagle-import") (part "TRANSISTOR-NPN-SOT23"))
    )
    (comp (ref "Q7")
      (value "BSS138")
      (footprint "eagle-import:SOT23")
      (libsource (lib "eagle-import") (part "MOSFET-N'SOT23'"))
    )
    (comp (ref "Q103")
      (value "S9013")
      (footprint "eagle-import:SOT23@1")
      (libsource (lib "eagle-import") (part "TRANSISTOR-NPN-SOT23"))
    )
    (comp (ref "Q104")
      (value "S9013")
      (footprint "eagle-import:SOT23@1")
      (libsource (lib "eagle-import") (part "TRANSISTOR-NPN-SOT23"))
    )
    (comp (ref "Q115")
      (value "S9013")
      (footprint "eagle-import:SOT23@1")
      (libsource (lib "eagle-import") (part "TRANSISTOR-NPN-SOT23"))
    )
    (comp (ref "Q405")
      (value "2N7002")
      (footprint "eagle-import:SOT23")
      (libsource (lib "eagle-import") (part "MOSFET-N'SOT23'"))
    )
    (comp (ref "R1")
      (value "10K")
      (footprint "eagle-import:R0603")
      (libsource (lib "eagle-import") (part "RESR0603"))
    )
    (comp (ref "R2")
      (value "1K")
      (footprint "eagle-import:R0603")
      (libsource (lib "eagle-import") (part "RESR0603"))
    )
    (comp (ref "R3")
      (value "4.7K 1%")
      (footprint "eagle-import:R0603")
      (libsource (lib "eagle-import") (part "RESR0603"))
    )
    (comp (ref "R4")
      (value "10K")
      (footprint "eagle-import:R0603")
      (libsource (lib "eagle-import") (part "RESR0603"))
    )
    (comp (ref "R5")
      (value "10k")
      (footprint "eagle-import:R0603")
      (libsource (lib "eagle-import") (part "RESR0603"))
    )
    (comp (ref "R6")
      (value "1K")
      (footprint "eagle-import:R0603")
      (libsource (lib "eagle-import") (part "RESR0603"))
    )
    (comp (ref "R7")
      (value "470R")
      (footprint "eagle-import:R0603")
      (libsource (lib "eagle-import") (part "RESR0603"))
    )
    (comp (ref "R8")
      (value "1k")
      (footprint "eagle-import:R0603")
      (libsource (lib "eagle-import") (part "RESR0603"))
    )
    (comp (ref "R9")
      (value "10K")
      (footprint "eagle-import:R0603")
      (libsource (lib "eagle-import") (part "RESR0603"))
    )
    (comp (ref "R10")
      (value "27.4R")
      (footprint "eagle-import:R0603")
      (libsource (lib "eagle-import") (part "RESR0603"))
    )
    (comp (ref "R11")
      (value "27.4R")
      (footprint "eagle-import:R0603")
      (libsource (lib "eagle-import") (part "RESR0603"))
    )
    (comp (ref "R12")
      (value "10K")
      (footprint "eagle-import:R0603")
      (libsource (lib "eagle-import") (part "RESR0603"))
    )
    (comp (ref "R13")
      (value "10K")
      (footprint "eagle-import:R0603")
      (libsource (lib "eagle-import") (part "RESR0603"))
    )
    (comp (ref "R14")
      (value "10K")
      (footprint "eagle-import:R0603")
      (libsource (lib "eagle-import") (part "RESR0603"))
    )
    (comp (ref "R15")
      (value "NC")
      (footprint "eagle-import:R0603")
      (libsource (lib "eagle-import") (part "RESR0603"))
    )
    (comp (ref "R16")
      (value "33R")
      (footprint "eagle-import:R0603")
      (libsource (lib "eagle-import") (part "RESR0603"))
    )
    (comp (ref "R17")
      (value "1K")
      (footprint "eagle-import:R0603")
      (libsource (lib "eagle-import") (part "RESR0603"))
    )
    (comp (ref "R18")
      (value "4.7K")
      (footprint "eagle-import:R0603")
      (libsource (lib "eagle-import") (part "RESR0603"))
    )
    (comp (ref "R19")
      (value "4.7K")
      (footprint "eagle-import:R0603")
      (libsource (lib "eagle-import") (part "RESR0603"))
    )
    (comp (ref "R20")
      (value "470R")
      (footprint "eagle-import:R0603")
      (libsource (lib "eagle-import") (part "RESR0603"))
    )
    (comp (ref "R21")
      (value "10K")
      (footprint "eagle-import:R0603")
      (libsource (lib "eagle-import") (part "RESR0603"))
    )
    (comp (ref "R22")
      (value "1K")
      (footprint "eagle-import:R0603")
      (libsource (lib "eagle-import") (part "RESR0603"))
    )
    (comp (ref "R23")
      (value "470R")
      (footprint "eagle-import:R0603")
      (libsource (lib "eagle-import") (part "RESR0603"))
    )
    (comp (ref "R24")
      (value "4.7K")
      (footprint "eagle-import:R0603")
      (libsource (lib "eagle-import") (part "RESR0603"))
    )
    (comp (ref "R25")
      (value "0R")
      (footprint "eagle-import:R0603")
      (libsource (lib "eagle-import") (part "RESR0603"))
    )
    (comp (ref "R26")
      (value "0R")
      (footprint "eagle-import:R0603")
      (libsource (lib "eagle-import") (part "RESR0603"))
    )
    (comp (ref "R27")
      (value "0R")
      (footprint "eagle-import:R0603")
      (libsource (lib "eagle-import") (part "RESR0603"))
    )
    (comp (ref "R28")
      (value "0R")
      (footprint "eagle-import:R0603")
      (libsource (lib "eagle-import") (part "RESR0603"))
    )
    (comp (ref "R29")
      (value "0R")
      (footprint "eagle-import:R0603")
      (libsource (lib "eagle-import") (part "RESR0603"))
    )
    (comp (ref "R34")
      (value "NC")
      (footprint "eagle-import:R0603")
      (libsource (lib "eagle-import") (part "RESR0603"))
    )
    (comp (ref "R35")
      (value "5.1R")
      (footprint "eagle-import:R0603")
      (libsource (lib "eagle-import") (part "RESR0603"))
    )
    (comp (ref "R36")
      (value "4.7K")
      (footprint "eagle-import:R0603")
      (libsource (lib "eagle-import") (part "RESR0603"))
    )
    (comp (ref "R40")
      (value "10R")
      (footprint "eagle-import:R0603")
      (libsource (lib "eagle-import") (part "RESR0603"))
    )
    (comp (ref "R41")
      (value "1K")
      (footprint "eagle-import:R0603")
      (libsource (lib "eagle-import") (part "RESR0603"))
    )
    (comp (ref "R42")
      (value "47K")
      (footprint "eagle-import:R0603")
      (libsource (lib "eagle-import") (part "RESR0603"))
    )
    (comp (ref "R43")
      (value "4.7k")
      (footprint "eagle-import:R0603")
      (libsource (lib "eagle-import") (part "RESR0603"))
    )
    (comp (ref "R44")
      (value "4.7k")
      (footprint "eagle-import:R0603")
      (libsource (lib "eagle-import") (part "RESR0603"))
    )
    (comp (ref "R45")
      (value "4.7k")
      (footprint "eagle-import:R0603")
      (libsource (lib "eagle-import") (part "RESR0603"))
    )
    (comp (ref "R46")
      (value "4.7k")
      (footprint "eagle-import:R0603")
      (libsource (lib "eagle-import") (part "RESR0603"))
    )
    (comp (ref "R47")
      (value "10k")
      (footprint "eagle-import:R0603")
      (libsource (lib "eagle-import") (part "RESR0603"))
    )
    (comp (ref "R54")
      (value "0R")
      (footprint "eagle-import:R0603")
      (libsource (lib "eagle-import") (part "RESR0603"))
    )
    (comp (ref "R56")
      (value "51K")
      (footprint "eagle-import:R0603")
      (libsource (lib "eagle-import") (part "RESR0603"))
    )
    (comp (ref "R57")
      (value "510K")
      (footprint "eagle-import:R0603")
      (libsource (lib "eagle-import") (part "RESR0603"))
    )
    (comp (ref "R58")
      (value "10K")
      (footprint "eagle-import:R0603")
      (libsource (lib "eagle-import") (part "RESR0603"))
    )
    (comp (ref "R59")
      (value "1K")
      (footprint "eagle-import:R0603")
      (libsource (lib "eagle-import") (part "RESR0603"))
    )
    (comp (ref "R61")
      (value "1K")
      (footprint "eagle-import:R0603")
      (libsource (lib "eagle-import") (part "RESR0603"))
    )
    (comp (ref "R62")
      (value "10K")
      (footprint "eagle-import:3P-SMD-SQUA-3.6X3.3")
      (libsource (lib "eagle-import") (part "R-POTENTIOMETER-SMD"))
    )
    (comp (ref "R63")
      (value "10K")
      (footprint "eagle-import:R0603")
      (libsource (lib "eagle-import") (part "RESR0603"))
    )
    (comp (ref "R76")
      (value "30.9K 1%")
      (footprint "eagle-import:R0603")
      (libsource (lib "eagle-import") (part "RESR0603"))
    )
    (comp (ref "R107")
      (value "10K")
      (footprint "eagle-import:R0603")
      (libsource (lib "eagle-import") (part "RESR0603"))
    )
    (comp (ref "R115")
      (value "10K")
      (footprint "eagle-import:R0603")
      (libsource (lib "eagle-import") (part "RESR0603"))
    )
    (comp (ref "R116")
      (value "10K")
      (footprint "eagle-import:R0603")
      (libsource (lib "eagle-import") (part "RESR0603"))
    )
    (comp (ref "R117")
      (value "14k")
      (footprint "eagle-import:R0603")
      (libsource (lib "eagle-import") (part "RESR0603"))
    )
    (comp (ref "R118")
      (value "NC")
      (footprint "eagle-import:R0603")
      (libsource (lib "eagle-import") (part "RESR0603"))
    )
    (comp (ref "R190")
      (value "3.3k")
      (footprint "eagle-import:R0603")
      (libsource (lib "eagle-import") (part "RESR0603"))
    )
    (comp (ref "R191")
      (value "10K")
      (footprint "eagle-import:R0603")
      (libsource (lib "eagle-import") (part "RESR0603"))
    )
    (comp (ref "R273")
      (value "10K")
      (footprint "eagle-import:R0603")
      (libsource (lib "eagle-import") (part "RESR0603"))
    )
    (comp (ref "R274")
      (value "1K")
      (footprint "eagle-import:R0603")
      (libsource (lib "eagle-import") (part "RESR0603"))
    )
    (comp (ref "R276")
      (value "22R")
      (footprint "eagle-import:R0603")
      (libsource (lib "eagle-import") (part "RESR0603"))
    )
    (comp (ref "R280")
      (value "10K")
      (footprint "eagle-import:R0603")
      (libsource (lib "eagle-import") (part "RESR0603"))
    )
    (comp (ref "R282")
      (value "2K")
      (footprint "eagle-import:R0603")
      (libsource (lib "eagle-import") (part "RESR0603"))
    )
    (comp (ref "R283")
      (value "22R")
      (footprint "eagle-import:R0603")
      (libsource (lib "eagle-import") (part "RESR0603"))
    )
    (comp (ref "R284")
      (value "2K")
      (footprint "eagle-import:R0603")
      (libsource (lib "eagle-import") (part "RESR0603"))
    )
    (comp (ref "R286")
      (value "10K")
      (footprint "eagle-import:R0603")
      (libsource (lib "eagle-import") (part "RESR0603"))
    )
    (comp (ref "R287")
      (value "1K")
      (footprint "eagle-import:R0603")
      (libsource (lib "eagle-import") (part "RESR0603"))
    )
    (comp (ref "R288")
      (value "10K")
      (footprint "eagle-import:R0603")
      (libsource (lib "eagle-import") (part "RESR0603"))
    )
    (comp (ref "R299")
      (value "2K")
      (footprint "eagle-import:R0603")
      (libsource (lib "eagle-import") (part "RESR0603"))
    )
    (comp (ref "R301")
      (value "10K")
      (footprint "eagle-import:R0603")
      (libsource (lib "eagle-import") (part "RESR0603"))
    )
    (comp (ref "R302")
      (value "10K")
      (footprint "eagle-import:R0603")
      (libsource (lib "eagle-import") (part "RESR0603"))
    )
    (comp (ref "R303")
      (value "22R")
      (footprint "eagle-import:R0603")
      (libsource (lib "eagle-import") (part "RESR0603"))
    )
    (comp (ref "R329")
      (value "NC")
      (footprint "eagle-import:R0603")
      (libsource (lib "eagle-import") (part "RESR0603"))
    )
    (comp (ref "R411")
      (value "30K/1%")
      (footprint "eagle-import:R0603")
      (libsource (lib "eagle-import") (part "RESR0603"))
    )
    (comp (ref "R412")
      (value "18K/1%")
      (footprint "eagle-import:R0603")
      (libsource (lib "eagle-import") (part "RESR0603"))
    )
    (comp (ref "R422")
      (value "4.7k")
      (footprint "eagle-import:R0603")
      (libsource (lib "eagle-import") (part "RESR0603"))
    )
    (comp (ref "R423")
      (value "4.7K")
      (footprint "eagle-import:R0603")
      (libsource (lib "eagle-import") (part "RESR0603"))
    )
    (comp (ref "R622")
      (value "200K")
      (footprint "eagle-import:R0603")
      (libsource (lib "eagle-import") (part "RESR0603"))
    )
    (comp (ref "R639")
      (value "1K")
      (footprint "eagle-import:R0603")
      (libsource (lib "eagle-import") (part "RESR0603"))
    )
    (comp (ref "R652")
      (value "2.7K")
      (footprint "eagle-import:R0603")
      (libsource (lib "eagle-import") (part "RESR0603"))
    )
    (comp (ref "R653")
      (value "3.74K")
      (footprint "eagle-import:R0603")
      (libsource (lib "eagle-import") (part "RESR0603"))
    )
    (comp (ref "R654")
      (value "5.6K")
      (footprint "eagle-import:R0603")
      (libsource (lib "eagle-import") (part "RESR0603"))
    )
    (comp (ref "R655")
      (value "8.2K")
      (footprint "eagle-import:R0603")
      (libsource (lib "eagle-import") (part "RESR0603"))
    )
    (comp (ref "RELAY1")
      (value "RELAY-SRD")
      (footprint "eagle-import:REY5-6-19.1X15.5X15.3MM")
      (libsource (lib "eagle-import") (part "RELAY-SRD"))
    )
    (comp (ref "RESET")
      (value "TS3425BA")
      (footprint "eagle-import:SMD_KEY4.2_3._.2.5")
      (libsource (lib "eagle-import") (part "KEY"))
    )
    (comp (ref "U1")
      (value "RP2350A")
      (footprint "eagle-import:QFN-60_7X7MM")
      (libsource (lib "eagle-import") (part "RP2350A"))
    )
    (comp (ref "U2")
      (value "APS6404L")
      (footprint "eagle-import:SOP-8L")
      (libsource (lib "eagle-import") (part "APS6404L"))
    )
    (comp (ref "U3")
      (value "W25Q64JVXGIQ")
      (footprint "eagle-import:W25QXX-XSON-8-EP(4X4)")
      (libsource (lib "eagle-import") (part "W25QXX"))
    )
    (comp (ref "U5")
      (value "DHT20")
      (footprint "eagle-import:CROWTAIL-DHT20-V1.0-20211013_DHT20")
      (libsource (lib "eagle-import") (part "CROWTAIL-DHT20-V1.0-20211013_DHT20"))
    )
    (comp (ref "U6")
      (value "HAL248")
      (footprint "eagle-import:SOT-23W")
      (libsource (lib "eagle-import") (part "A1101"))
    )
    (comp (ref "U7")
      (value "BH1750")
      (footprint "eagle-import:BH1750-WSOF-6")
      (libsource (lib "eagle-import") (part "BH1750"))
    )
    (comp (ref "U10")
      (value "SN74LVC1G125")
      (footprint "eagle-import:SOT23-5")
      (libsource (lib "eagle-import") (part "SN74LVC1G125"))
    )
    (comp (ref "U11")
      (value "LM393")
      (footprint "eagle-import:SOP8@1")
      (libsource (lib "eagle-import") (part "IC_LM393_SOP8"))
    )
    (comp (ref "U12")
      (value "MPU-6050-1")
      (footprint "eagle-import:QFN-24-4MM2")
      (libsource (lib "eagle-import") (part "MPU-6050-1"))
    )
    (comp (ref "U30")
      (value "MT2492")
      (footprint "eagle-import:MT2492-SOT23-6")
      (libsource (lib "eagle-import") (part "MT2492"))
    )
    (comp (ref "U34")
      (value "LPW5206AB5F")
      (footprint "eagle-import:IC_SOT23-5")
      (libsource (lib "eagle-import") (part "LPW5206B5F_SOT23-5"))
    )
    (comp (ref "U41")
      (value "PW1503")
      (footprint "eagle-import:SOT23-5")
      (libsource (lib "eagle-import") (part "PW1503"))
    )
    (comp (ref "U123")
      (value "TTP223")
      (footprint "eagle-import:SOT23-6L")
      (libsource (lib "eagle-import") (part "TTP223"))
    )
    (comp (ref "U309")
      (value "IR-3PSIP3")
      (footprint "eagle-import:VS1838B-SIP3")
      (libsource (lib "eagle-import") (part "IR-3PSIP3"))
    )
    (comp (ref "U401")
      (value "TD1509")
      (footprint "eagle-import:TD1509")
      (libsource (lib "eagle-import") (part "TD1509"))
    )
    (comp (ref "X1")
      (value "X322512MSB4SI")
      (footprint "eagle-import:A_XBJ_SMD3225")
      (libsource (lib "eagle-import") (part "A_XBJ_XTAL"))
    )
  )
  (nets
    (net (code "1") (name "+1V1") (class "Default")
      (node (ref "C15") (pin "1") (pinfunction "1_1") (pintype "passive"))
      (node (ref "C24") (pin "1") (pinfunction "1_1") (pintype "passive"))
      (node (ref "C26") (pin "2") (pinfunction "2_2") (pintype "passive"))
      (node (ref "C4") (pin "1") (pinfunction "1_1") (pintype "passive"))
      (node (ref "L1") (pin "P$1") (pinfunction "1_P$1") (pintype "passive"))
      (node (ref "U1") (pin "P$23") (pinfunction "DVDD1_P$23") (pintype "power_in"))
      (node (ref "U1") (pin "P$39") (pinfunction "DVDD0_P$39") (pintype "power_in"))
      (node (ref "U1") (pin "P$50") (pinfunction "VREG_FB_P$50") (pintype "bidirectional"))
      (node (ref "U1") (pin "P$6") (pinfunction "DVDD2_P$6") (pintype "power_in"))
    )
    (net (code "2") (name "/COM") (class "Default")
      (node (ref "J123") (pin "2") (pinfunction "P$2_2") (pintype "bidirectional"))
      (node (ref "RELAY1") (pin "2") (pinfunction "2_2") (pintype "bidirectional"))
    )
    (net (code "3") (name "/DC_OUT1") (class "Default")
      (node (ref "D007") (pin "C") (pinfunction "C_C") (pintype "passive"))
      (node (ref "L401") (pin "1") (pinfunction "1_1") (pintype "bidirectional"))
      (node (ref "U401") (pin "P$2") (pinfunction "2_VOUT_P$2") (pintype "bidirectional"))
    )
    (net (code "4") (name "/FB1") (class "Default")
      (node (ref "C412") (pin "1") (pinfunction "1_1") (pintype "passive"))
      (node (ref "R411") (pin "1") (pinfunction "1_1") (pintype "passive"))
      (node (ref "R412") (pin "2") (pinfunction "2_2") (pintype "passive"))
      (node (ref "U401") (pin "P$3") (pinfunction "3_FB_P$3") (pintype "bidirectional"))
    )
    (net (code "5") (name "/IO1_HALL") (class "Default")
      (node (ref "C34") (pin "2") (pinfunction "2_2") (pintype "passive"))
      (node (ref "Q7") (pin "3") (pinfunction "D_3") (pintype "passive"))
      (node (ref "R34") (pin "2") (pinfunction "2_2") (pintype "passive"))
      (node (ref "R63") (pin "1") (pinfunction "1_1") (pintype "passive"))
      (node (ref "U6") (pin "2") (pinfunction "VOUT_2") (pintype "output"))
    )
    (net (code "6") (name "/IO_RGB_OUT") (class "Default")
      (node (ref "D183") (pin "4") (pinfunction "4_DIN_4") (pintype "bidirectional"))
      (node (ref "U10") (pin "4") (pinfunction "Y_4") (pintype "bidirectional"))
    )
    (net (code "7") (name "/NC") (class "Default")
      (node (ref "J123") (pin "1") (pinfunction "P$1_1") (pintype "bidirectional"))
      (node (ref "RELAY1") (pin "4") (pinfunction "4_4") (pintype "bidirectional"))
    )
    (net (code "8") (name "/NO") (class "Default")
      (node (ref "J123") (pin "3") (pinfunction "P$3_3") (pintype "bidirectional"))
      (node (ref "RELAY1") (pin "5") (pinfunction "5_5") (pintype "bidirectional"))
    )
    (net (code "9") (name "/SERVO") (class "Default")
      (node (ref "J1") (pin "1") (pinfunction "1_1") (pintype "bidirectional"))
      (node (ref "P12") (pin "P$1") (pinfunction "P$1_P$1") (pintype "bidirectional"))
      (node (ref "Q405") (pin "3") (pinfunction "D_3") (pintype "passive"))
      (node (ref "R329") (pin "1") (pinfunction "1_1") (pintype "passive"))
      (node (ref "R423") (pin "2") (pinfunction "2_2") (pintype "passive"))
    )
    (net (code "10") (name "/V+") (class "Default")
      (node (ref "R276") (pin "2") (pinfunction "2_2") (pintype "passive"))
      (node (ref "RELAY1") (pin "1") (pinfunction "1_1") (pintype "bidirectional"))
    )
    (net (code "11") (name "/V-") (class "Default")
      (node (ref "D002") (pin "+") (pinfunction "+_+") (pintype "passive"))
      (node (ref "LED1") (pin "-") (pinfunction "-_-") (pintype "passive"))
      (node (ref "Q115") (pin "3") (pinfunction "C_3") (pintype "passive"))
      (node (ref "RELAY1") (pin "3") (pinfunction "3_3") (pintype "bidirectional"))
    )
    (net (code "12") (name "/VCC_RELAY") (class "Default")
      (node (ref "C36") (pin "2") (pinfunction "2_2") (pintype "passive"))
      (node (ref "D002") (pin "-") (pinfunction "-_-") (pintype "passive"))
      (node (ref "L11") (pin "2") (pinfunction "2_2") (pintype "bidirectional"))
      (node (ref "R24") (pin "2") (pinfunction "2_2") (pintype "passive"))
      (node (ref "R276") (pin "1") (pinfunction "1_1") (pintype "passive"))
    )
    (net (code "13") (name "BOOT") (class "Default")
      (node (ref "BOOT") (pin "P$1") (pinfunction "1_P$1") (pintype "bidirectional"))
      (node (ref "R2") (pin "2") (pinfunction "2_2") (pintype "passive"))
    )
    (net (code "14") (name "CORE_RESET") (class "Default")
      (node (ref "C14") (pin "2") (pinfunction "2_2") (pintype "passive"))
      (node (ref "D001") (pin "-") (pinfunction "-_-") (pintype "passive"))
      (node (ref "R5") (pin "1") (pinfunction "1_1") (pintype "passive"))
      (node (ref "RESET") (pin "P$2") (pinfunction "2_P$2") (pintype "bidirectional"))
      (node (ref "U1") (pin "P$26") (pinfunction "RUN_P$26") (pintype "bidirectional"))
    )
    (net (code "15") (name "GND") (class "Default")
      (node (ref "BOOT") (pin "P$4") (pinfunction "4_P$4") (pintype "bidirectional"))
      (node (ref "C1") (pin "1") (pinfunction "1_1") (pintype "passive"))
      (node (ref "C10") (pin "2") (pinfunction "2_2") (pintype "passive"))
      (node (ref "C11") (pin "2") (pinfunction "2_2") (pintype "passive"))
      (node (ref "C12") (pin "2") (pinfunction "2_2") (pintype "passive"))
      (node (ref "C13") (pin "2") (pinfunction "2_2") (pintype "passive"))
      (node (ref "C14") (pin "1") (pinfunction "1_1") (pintype "passive"))
      (node (ref "C15") (pin "2") (pinfunction "2_2") (pintype "passive"))
      (node (ref "C16") (pin "2") (pinfunction "2_2") (pintype "passive"))
      (node (ref "C17") (pin "2") (pinfunction "2_2") (pintype "passive"))
      (node (ref "C18") (pin "1") (pinfunction "1_1") (pintype "passive"))
      (node (ref "C183") (pin "2") (pinfunction "2_2") (pintype "passive"))
      (node (ref "C19") (pin "2") (pinfunction "2_2") (pintype "passive"))
      (node (ref "C2") (pin "2") (pinfunction "2_2") (pintype "passive"))
      (node (ref "C20") (pin "2") (pinfunction "2_2") (pintype "passive"))
      (node (ref "C21") (pin "2") (pinfunction "2_2") (pintype "passive"))
      (node (ref "C212") (pin "1") (pinfunction "1_1") (pintype "passive"))
      (node (ref "C213") (pin "1") (pinfunction "1_1") (pintype "passive"))
      (node (ref "C214") (pin "1") (pinfunction "1_1") (pintype "passive"))
      (node (ref "C22") (pin "2") (pinfunction "2_2") (pintype "passive"))
      (node (ref "C23") (pin "2") (pinfunction "2_2") (pintype "passive"))
      (node (ref "C24") (pin "2") (pinfunction "2_2") (pintype "passive"))
      (node (ref "C25") (pin "1") (pinfunction "1_1") (pintype "passive"))
      (node (ref "C26") (pin "1") (pinfunction "1_1") (pintype "passive"))
      (node (ref "C27") (pin "2") (pinfunction "2_2") (pintype "passive"))
      (node (ref "C28") (pin "2") (pinfunction "2_2") (pintype "passive"))
      (node (ref "C29") (pin "2") (pinfunction "2_2") (pintype "passive"))
      (node (ref "C3") (pin "1") (pinfunction "1_1") (pintype "passive"))
      (node (ref "C30") (pin "2") (pinfunction "2_2") (pintype "passive"))
      (node (ref "C31") (pin "1") (pinfunction "1_1") (pintype "passive"))
      (node (ref "C32") (pin "1") (pinfunction "1_1") (pintype "passive"))
      (node (ref "C33") (pin "1") (pinfunction "1_1") (pintype "passive"))
      (node (ref "C34") (pin "1") (pinfunction "1_1") (pintype "passive"))
      (node (ref "C35") (pin "1") (pinfunction "1_1") (pintype "passive"))
      (node (ref "C36") (pin "1") (pinfunction "1_1") (pintype "passive"))
      (node (ref "C37") (pin "1") (pinfunction "1_1") (pintype "passive"))
      (node (ref "C38") (pin "1") (pinfunction "1_1") (pintype "passive"))
      (node (ref "C39") (pin "1") (pinfunction "1_1") (pintype "passive"))
      (node (ref "C4") (pin "2") (pinfunction "2_2") (pintype "passive"))
      (node (ref "C40") (pin "1") (pinfunction "1_1") (pintype "passive"))
      (node (ref "C409") (pin "1") (pinfunction "1_1") (pintype "passive"))
      (node (ref "C41") (pin "1") (pinfunction "1_1") (pintype "passive"))
      (node (ref "C411") (pin "1") (pinfunction "1_1") (pintype "passive"))
      (node (ref "C413") (pin "2") (pinfunction "2_2") (pintype "passive"))
      (node (ref "C414") (pin "2") (pinfunction "2_2") (pintype "passive"))
      (node (ref "C42") (pin "1") (pinfunction "1_1") (pintype "passive"))
      (node (ref "C43") (pin "1") (pinfunction "1_1") (pintype "passive"))
      (node (ref "C44") (pin "2") (pinfunction "2_2") (pintype "passive"))
      (node (ref "C45") (pin "1") (pinfunction "1_1") (pintype "passive"))
      (node (ref "C46") (pin "2") (pinfunction "2_2") (pintype "passive"))
      (node (ref "C47") (pin "1") (pinfunction "1_1") (pintype "passive"))
      (node (ref "C48") (pin "1") (pinfunction "1_1") (pintype "passive"))
      (node (ref "C49") (pin "1") (pinfunction "1_1") (pintype "passive"))
      (node (ref "C5") (pin "1") (pinfunction "1_1") (pintype "passive"))
      (node (ref "C50") (pin "1") (pinfunction "1_1") (pintype "passive"))
      (node (ref "C51") (pin "2") (pinfunction "2_2") (pintype "passive"))
      (node (ref "C57") (pin "2") (pinfunction "2_2") (pintype "passive"))
      (node (ref "C6") (pin "1") (pinfunction "1_1") (pintype "passive"))
      (node (ref "C64") (pin "1") (pinfunction "1_1") (pintype "passive"))
      (node (ref "C66") (pin "2") (pinfunction "2_2") (pintype "passive"))
      (node (ref "C67") (pin "1") (pinfunction "1_1") (pintype "passive"))
      (node (ref "C68") (pin "1") (pinfunction "1_1") (pintype "passive"))
      (node (ref "C69") (pin "1") (pinfunction "1_1") (pintype "passive"))
      (node (ref "C7") (pin "1") (pinfunction "1_1") (pintype "passive"))
      (node (ref "C70") (pin "1") (pinfunction "1_1") (pintype "passive"))
      (node (ref "C71") (pin "1") (pinfunction "1_1") (pintype "passive"))
      (node (ref "C8") (pin "2") (pinfunction "2_2") (pintype "passive"))
      (node (ref "C90") (pin "2") (pinfunction "2_2") (pintype "passive"))
      (node (ref "D007") (pin "A") (pinfunction "A_A") (pintype "passive"))
      (node (ref "D012") (pin "3") (pinfunction "3_GND_3") (pintype "bidirectional"))
      (node (ref "D019") (pin "3") (pinfunction "3_GND_3") (pintype "bidirectional"))
      (node (ref "D021") (pin "3") (pinfunction "3_GND_3") (pintype "bidirectional"))
      (node (ref "D022") (pin "3") (pinfunction "3_GND_3") (pintype "bidirectional"))
      (node (ref "D023") (pin "3") (pinfunction "3_GND_3") (pintype "bidirectional"))
      (node (ref "D024") (pin "3") (pinfunction "3_GND_3") (pintype "bidirectional"))
      (node (ref "D025") (pin "3") (pinfunction "3_GND_3") (pintype "bidirectional"))
      (node (ref "D026") (pin "3") (pinfunction "3_GND_3") (pintype "bidirectional"))
      (node (ref "D027") (pin "3") (pinfunction "3_GND_3") (pintype "bidirectional"))
      (node (ref "D028") (pin "3") (pinfunction "3_GND_3") (pintype "bidirectional"))
      (node (ref "D029") (pin "3") (pinfunction "3_GND_3") (pintype "bidirectional"))
      (node (ref "D030") (pin "3") (pinfunction "3_GND_3") (pintype "bidirectional"))
      (node (ref "D031") (pin "3") (pinfunction "3_GND_3") (pintype "bidirectional"))
      (node (ref "D032") (pin "3") (pinfunction "3_GND_3") (pintype "bidirectional"))
      (node (ref "D033") (pin "3") (pinfunction "3_GND_3") (pintype "bidirectional"))
      (node (ref "D183") (pin "3") (pinfunction "3_GND_3") (pintype "bidirectional"))
      (node (ref "D184") (pin "3") (pinfunction "3_GND_3") (pintype "bidirectional"))
      (node (ref "D185") (pin "3") (pinfunction "3_GND_3") (pintype "bidirectional"))
      (node (ref "D186") (pin "3") (pinfunction "3_GND_3") (pintype "bidirectional"))
      (node (ref "D187") (pin "3") (pinfunction "3_GND_3") (pintype "bidirectional"))
      (node (ref "FPC1") (pin "P$1") (pinfunction "GND_P$1") (pintype "bidirectional"))
      (node (ref "FPC1") (pin "P$16") (pinfunction "GND_P$16") (pintype "bidirectional"))
      (node (ref "FPC1") (pin "P$17") (pinfunction "G2_P$17") (pintype "bidirectional"))
      (node (ref "FPC1") (pin "P$18") (pinfunction "G1_P$18") (pintype "bidirectional"))
      (node (ref "J1") (pin "4") (pinfunction "4_4") (pintype "bidirectional"))
      (node (ref "J1") (pin "SS1") (pinfunction "SS1_SS1") (pintype "bidirectional"))
      (node (ref "J1") (pin "SS2") (pinfunction "SS2_SS2") (pintype "bidirectional"))
      (node (ref "J14") (pin "P$1") (pinfunction "1_GND_P$1") (pintype "bidirectional"))
      (node (ref "J3") (pin "2") (pinfunction "-_2") (pintype "bidirectional"))
      (node (ref "J7") (pin "1") (pinfunction "1_1") (pintype "bidirectional"))
      (node (ref "J8") (pin "4") (pinfunction "4_4") (pintype "bidirectional"))
      (node (ref "J8") (pin "5") (pinfunction "SS1_5") (pintype "bidirectional"))
      (node (ref "J8") (pin "6") (pinfunction "SS2_6") (pintype "bidirectional"))
      (node (ref "K1") (pin "P$1") (pinfunction "P$1_P$1") (pintype "bidirectional"))
      (node (ref "K2") (pin "P$1") (pinfunction "P$1_P$1") (pintype "bidirectional"))
      (node (ref "K3") (pin "P$1") (pinfunction "P$1_P$1") (pintype "bidirectional"))
      (node (ref "K4") (pin "P$1") (pinfunction "P$1_P$1") (pintype "bidirectional"))
      (node (ref "P11") (pin "P$1") (pinfunction "P$1_P$1") (pintype "bidirectional"))
      (node (ref "P2") (pin "1") (pinfunction "1_1") (pintype "passive"))
      (node (ref "P24") (pin "P$1") (pinfunction "P$1_P$1") (pintype "bidirectional"))
      (node (ref "P4") (pin "P$1") (pinfunction "P$1_P$1") (pintype "bidirectional"))
      (node (ref "P9") (pin "P$1") (pinfunction "P$1_P$1") (pintype "bidirectional"))
      (node (ref "Q1") (pin "2") (pinfunction "E_2") (pintype "passive"))
      (node (ref "Q103") (pin "2") (pinfunction "E_2") (pintype "passive"))
      (node (ref "Q104") (pin "2") (pinfunction "E_2") (pintype "passive"))
      (node (ref "Q115") (pin "2") (pinfunction "E_2") (pintype "passive"))
      (node (ref "Q2") (pin "2") (pinfunction "E_2") (pintype "passive"))
      (node (ref "Q3") (pin "2") (pinfunction "E_2") (pintype "passive"))
      (node (ref "Q5") (pin "2") (pinfunction "E_2") (pintype "passive"))
      (node (ref "Q6") (pin "2") (pinfunction "E_2") (pintype "passive"))
      (node (ref "R115") (pin "2") (pinfunction "2_2") (pintype "passive"))
      (node (ref "R117") (pin "2") (pinfunction "2_2") (pintype "passive"))
      (node (ref "R13") (pin "1") (pinfunction "1_1") (pintype "passive"))
      (node (ref "R15") (pin "1") (pinfunction "1_1") (pintype "passive"))
      (node (ref "R190") (pin "2") (pinfunction "2_2") (pintype "passive"))
      (node (ref "R21") (pin "1") (pinfunction "1_1") (pintype "passive"))
      (node (ref "R273") (pin "1") (pinfunction "1_1") (pintype "passive"))
      (node (ref "R280") (pin "1") (pinfunction "1_1") (pintype "passive"))
      (node (ref "R286") (pin "2") (pinfunction "2_2") (pintype "passive"))
      (node (ref "R288") (pin "2") (pinfunction "2_2") (pintype "passive"))
      (node (ref "R3") (pin "1") (pinfunction "1_1") (pintype "passive"))
      (node (ref "R302") (pin "1") (pinfunction "1_1") (pintype "passive"))
      (node (ref "R35") (pin "1") (pinfunction "1_1") (pintype "passive"))
      (node (ref "R36") (pin "2") (pinfunction "2_2") (pintype "passive"))
      (node (ref "R4") (pin "1") (pinfunction "1_1") (pintype "passive"))
      (node (ref "R412") (pin "1") (pinfunction "1_1") (pintype "passive"))
      (node (ref "R42") (pin "2") (pinfunction "2_2") (pintype "passive"))
      (node (ref "R56") (pin "2") (pinfunction "2_2") (pintype "passive"))
      (node (ref "R62") (pin "1") (pinfunction "1_1") (pintype "passive"))
      (node (ref "R622") (pin "2") (pinfunction "2_2") (pintype "passive"))
      (node (ref "RESET") (pin "P$3") (pinfunction "3_P$3") (pintype "bidirectional"))
      (node (ref "U1") (pin "P$47") (pinfunction "VREG_PGND_P$47") (pintype "bidirectional"))
      (node (ref "U1") (pin "P$61") (pinfunction "GND_P$61") (pintype "bidirectional"))
      (node (ref "U10") (pin "1") (pinfunction "OE_1") (pintype "bidirectional"))
      (node (ref "U10") (pin "3") (pinfunction "GND_3") (pintype "bidirectional"))
      (node (ref "U11") (pin "4") (pinfunction "4_GND_4") (pintype "bidirectional"))
      (node (ref "U12") (pin "1") (pinfunction "CLKIN_1") (pintype "bidirectional"))
      (node (ref "U12") (pin "11") (pinfunction "FSYNC_11") (pintype "bidirectional"))
      (node (ref "U12") (pin "18") (pinfunction "GND_18") (pintype "bidirectional"))
      (node (ref "U12") (pin "9") (pinfunction "AD0_9") (pintype "bidirectional"))
      (node (ref "U123") (pin "2") (pinfunction "GND_2") (pintype "bidirectional"))
      (node (ref "U2") (pin "P$4") (pinfunction "VSS_P$4") (pintype "bidirectional"))
      (node (ref "U3") (pin "4") (pinfunction "GND_4") (pintype "bidirectional"))
      (node (ref "U3") (pin "EP") (pinfunction "GND_EP") (pintype "bidirectional"))
      (node (ref "U30") (pin "2") (pinfunction "GND_2") (pintype "bidirectional"))
      (node (ref "U309") (pin "2") (pinfunction "P$2_2") (pintype "bidirectional"))
      (node (ref "U34") (pin "2") (pinfunction "2_GND_2") (pintype "bidirectional"))
      (node (ref "U401") (pin "P$4") (pinfunction "4_EN_P$4") (pintype "bidirectional"))
      (node (ref "U401") (pin "P$5") (pinfunction "5_GND_P$5") (pintype "bidirectional"))
      (node (ref "U401") (pin "P$6") (pinfunction "6_GND_P$6") (pintype "bidirectional"))
      (node (ref "U401") (pin "P$7") (pinfunction "7_GND_P$7") (pintype "bidirectional"))
      (node (ref "U401") (pin "P$8") (pinfunction "8_GND_P$8") (pintype "bidirectional"))
      (node (ref "U41") (pin "2") (pinfunction "GND_2") (pintype "bidirectional"))
      (node (ref "U5") (pin "3") (pinfunction "GND_3") (pintype "bidirectional"))
      (node (ref "U6") (pin "3") (pinfunction "GND_3") (pintype "power_in"))
      (node (ref "U7") (pin "3") (pinfunction "GND\\_3") (pintype "bidirectional"))
      (node (ref "X1") (pin "2") (pinfunction "GND_2") (pintype "bidirectional"))
      (node (ref "X1") (pin "4") (pinfunction "GND_4") (pintype "bidirectional"))
    )
    (net (code "16") (name "GP0_LED_BK") (class "Default")
      (node (ref "R41") (pin "2") (pinfunction "2_2") (pintype "passive"))
      (node (ref "U1") (pin "P$2") (pinfunction "GPIO0_P$2") (pintype "bidirectional"))
    )
    (net (code "17") (name "GP1_PSRAM_CS") (class "Default")
      (node (ref "R14") (pin "1") (pinfunction "1_1") (pintype "passive"))
      (node (ref "U1") (pin "P$3") (pinfunction "GPIO1_P$3") (pintype "bidirectional"))
      (node (ref "U2") (pin "P$1") (pinfunction "/CE_P$1") (pintype "bidirectional"))
    )
    (net (code "18") (name "GP2{slash}I2C1_SDA") (class "Default")
      (node (ref "R18") (pin "2") (pinfunction "2_2") (pintype "passive"))
      (node (ref "R26") (pin "2") (pinfunction "2_2") (pintype "passive"))
      (node (ref "U12") (pin "24") (pinfunction "SDA_24") (pintype "bidirectional"))
      (node (ref "U5") (pin "2") (pinfunction "SDA_2") (pintype "bidirectional"))
      (node (ref "U7") (pin "4") (pinfunction "SDA_4") (pintype "bidirectional"))
    )
    (net (code "19") (name "GP3{slash}I2C1_SCL") (class "Default")
      (node (ref "R19") (pin "2") (pinfunction "2_2") (pintype "passive"))
      (node (ref "R27") (pin "2") (pinfunction "2_2") (pintype "passive"))
      (node (ref "U12") (pin "23") (pinfunction "SCL_23") (pintype "bidirectional"))
      (node (ref "U5") (pin "4") (pinfunction "SCL_4") (pintype "bidirectional"))
      (node (ref "U7") (pin "6") (pinfunction "SCL_6") (pintype "bidirectional"))
    )
    (net (code "20") (name "GP4{slash}I2C0_SDA") (class "Default")
      (node (ref "FPC1") (pin "P$4") (pinfunction "YD/CTP_SDA_P$4") (pintype "bidirectional"))
      (node (ref "P16") (pin "P$1") (pinfunction "P$1_P$1") (pintype "bidirectional"))
      (node (ref "R28") (pin "2") (pinfunction "2_2") (pintype "passive"))
      (node (ref "R45") (pin "1") (pinfunction "1_1") (pintype "passive"))
    )
    (net (code "21") (name "GP5{slash}I2C0_SCL") (class "Default")
      (node (ref "FPC1") (pin "P$3") (pinfunction "XR/CTP_SCL_P$3") (pintype "bidirectional"))
      (node (ref "P15") (pin "P$1") (pinfunction "P$1_P$1") (pintype "bidirectional"))
      (node (ref "R29") (pin "2") (pinfunction "2_2") (pintype "passive"))
      (node (ref "R46") (pin "1") (pinfunction "1_1") (pintype "passive"))
    )
    (net (code "22") (name "GP6_SPI0_CLK_TFT") (class "Default")
      (node (ref "FPC1") (pin "P$13") (pinfunction "SCL_P$13") (pintype "bidirectional"))
      (node (ref "P21") (pin "P$1") (pinfunction "P$1_P$1") (pintype "bidirectional"))
      (node (ref "R43") (pin "1") (pinfunction "1_1") (pintype "passive"))
      (node (ref "U1") (pin "P$9") (pinfunction "GPIO6_P$9") (pintype "bidirectional"))
    )
    (net (code "23") (name "GP7_SPI0_MOSI_TFT") (class "Default")
      (node (ref "FPC1") (pin "P$14") (pinfunction "SDI_P$14") (pintype "bidirectional"))
      (node (ref "P22") (pin "P$1") (pinfunction "P$1_P$1") (pintype "bidirectional"))
      (node (ref "R44") (pin "1") (pinfunction "1_1") (pintype "passive"))
      (node (ref "U1") (pin "P$10") (pinfunction "GPIO7_P$10") (pintype "bidirectional"))
    )
    (net (code "24") (name "GP16_RS_TFT") (class "Default")
      (node (ref "FPC1") (pin "P$7") (pinfunction "RS_P$7") (pintype "bidirectional"))
      (node (ref "P19") (pin "P$1") (pinfunction "P$1_P$1") (pintype "bidirectional"))
      (node (ref "U1") (pin "P$27") (pinfunction "GPIO16_P$27") (pintype "bidirectional"))
    )
    (net (code "25") (name "GP17_SPI0_CS_TFT") (class "Default")
      (node (ref "FPC1") (pin "P$12") (pinfunction "CS_P$12") (pintype "bidirectional"))
      (node (ref "P20") (pin "P$1") (pinfunction "P$1_P$1") (pintype "bidirectional"))
      (node (ref "U1") (pin "P$28") (pinfunction "GPIO17_P$28") (pintype "bidirectional"))
    )
    (net (code "26") (name "GP26_A0_GAS") (class "Default")
      (node (ref "J2") (pin "4") (pinfunction "B_4") (pintype "bidirectional"))
      (node (ref "J2") (pin "6") (pinfunction "B_6") (pintype "bidirectional"))
      (node (ref "R36") (pin "1") (pinfunction "1_1") (pintype "passive"))
      (node (ref "U1") (pin "P$40") (pinfunction "GPIO26_ADC0_P$40") (pintype "bidirectional"))
    )
    (net (code "27") (name "GP27_A1_KEY") (class "Default")
      (node (ref "P61") (pin "P$1") (pinfunction "P$1_P$1") (pintype "bidirectional"))
      (node (ref "R639") (pin "2") (pinfunction "2_2") (pintype "passive"))
      (node (ref "R652") (pin "2") (pinfunction "2_2") (pintype "passive"))
      (node (ref "R653") (pin "2") (pinfunction "2_2") (pintype "passive"))
      (node (ref "R654") (pin "2") (pinfunction "2_2") (pintype "passive"))
      (node (ref "R655") (pin "2") (pinfunction "2_2") (pintype "passive"))
      (node (ref "U1") (pin "P$41") (pinfunction "GPIO27_ADC1_P$41") (pintype "bidirectional"))
    )
    (net (code "28") (name "GP28_A2_POT") (class "Default")
      (node (ref "C18") (pin "2") (pinfunction "2_2") (pintype "passive"))
      (node (ref "C40") (pin "2") (pinfunction "2_2") (pintype "passive"))
      (node (ref "P2") (pin "2") (pinfunction "3_2") (pintype "passive"))
      (node (ref "U1") (pin "P$42") (pinfunction "GPIO28_ADC2_P$42") (pintype "bidirectional"))
    )
    (net (code "29") (name "GP29_A3_SOUND") (class "Default")
      (node (ref "P30") (pin "P$1") (pinfunction "P$1_P$1") (pintype "bidirectional"))
      (node (ref "R61") (pin "1") (pinfunction "1_1") (pintype "passive"))
      (node (ref "U1") (pin "P$43") (pinfunction "GPIO29_ADC3_P$43") (pintype "bidirectional"))
      (node (ref "U11") (pin "1") (pinfunction "1_OUT1_1") (pintype "bidirectional"))
    )
    (net (code "30") (name "GPIO8_US_ECHO") (class "Default")
      (node (ref "R299") (pin "2") (pinfunction "2_2") (pintype "passive"))
      (node (ref "U1") (pin "P$12") (pinfunction "GPIO8_P$12") (pintype "bidirectional"))
    )
    (net (code "31") (name "GPIO9_US_TRIG") (class "Default")
      (node (ref "J14") (pin "P$3") (pinfunction "3_TRIG_P$3") (pintype "bidirectional"))
      (node (ref "U1") (pin "P$13") (pinfunction "GPIO9_P$13") (pintype "bidirectional"))
    )
    (net (code "32") (name "GPIO10_BUZZER") (class "Default")
      (node (ref "R284") (pin "1") (pinfunction "1_1") (pintype "passive"))
      (node (ref "U1") (pin "P$14") (pinfunction "GPIO10_P$14") (pintype "bidirectional"))
    )
    (net (code "33") (name "GPIO11_IR") (class "Default")
      (node (ref "R301") (pin "2") (pinfunction "2_2") (pintype "passive"))
      (node (ref "U1") (pin "P$15") (pinfunction "GPIO11_P$15") (pintype "bidirectional"))
      (node (ref "U309") (pin "3") (pinfunction "P$3_3") (pintype "bidirectional"))
    )
    (net (code "34") (name "GPIO12_RELAY") (class "Default")
      (node (ref "R274") (pin "2") (pinfunction "2_2") (pintype "passive"))
      (node (ref "U1") (pin "P$16") (pinfunction "GPIO12_P$16") (pintype "bidirectional"))
    )
    (net (code "35") (name "GPIO13_SERVO") (class "Default")
      (node (ref "P53") (pin "P$1") (pinfunction "P$1_P$1") (pintype "bidirectional"))
      (node (ref "Q405") (pin "2") (pinfunction "S_2") (pintype "passive"))
      (node (ref "R329") (pin "2") (pinfunction "2_2") (pintype "passive"))
      (node (ref "R422") (pin "1") (pinfunction "1_1") (pintype "passive"))
      (node (ref "U1") (pin "P$17") (pinfunction "GPIO13_P$17") (pintype "bidirectional"))
    )
    (net (code "36") (name "GPIO14_TOUCH") (class "Default")
      (node (ref "P55") (pin "P$1") (pinfunction "P$1_P$1") (pintype "bidirectional"))
      (node (ref "R287") (pin "2") (pinfunction "2_2") (pintype "passive"))
      (node (ref "U1") (pin "P$18") (pinfunction "GPIO14_P$18") (pintype "bidirectional"))
    )
    (net (code "37") (name "GPIO15_VIB") (class "Default")
      (node (ref "R25") (pin "2") (pinfunction "2_2") (pintype "passive"))
      (node (ref "U1") (pin "P$19") (pinfunction "GPIO15_P$19") (pintype "bidirectional"))
    )
    (net (code "38") (name "GPIO18_LED_RED") (class "Default")
      (node (ref "R6") (pin "2") (pinfunction "2_2") (pintype "passive"))
      (node (ref "U1") (pin "P$29") (pinfunction "GPIO18_P$29") (pintype "bidirectional"))
    )
    (net (code "39") (name "GPIO19_LED_GREEN") (class "Default")
      (node (ref "R17") (pin "2") (pinfunction "2_2") (pintype "passive"))
      (node (ref "U1") (pin "P$31") (pinfunction "GPIO19_P$31") (pintype "bidirectional"))
    )
    (net (code "40") (name "GPIO20_LED_YELLOW") (class "Default")
      (node (ref "R22") (pin "2") (pinfunction "2_2") (pintype "passive"))
      (node (ref "U1") (pin "P$32") (pinfunction "GPIO20_P$32") (pintype "bidirectional"))
    )
    (net (code "41") (name "GPIO21_HALL") (class "Default")
      (node (ref "Q7") (pin "2") (pinfunction "S_2") (pintype "passive"))
      (node (ref "R107") (pin "1") (pinfunction "1_1") (pintype "passive"))
      (node (ref "R34") (pin "1") (pinfunction "1_1") (pintype "passive"))
      (node (ref "U1") (pin "P$33") (pinfunction "GPIO21_P$33") (pintype "bidirectional"))
    )
    (net (code "42") (name "GPIO22_RGB") (class "Default")
      (node (ref "R54") (pin "1") (pinfunction "1_1") (pintype "passive"))
      (node (ref "U1") (pin "P$34") (pinfunction "GPIO22_P$34") (pintype "bidirectional"))
    )
    (net (code "43") (name "GPIO23_RGB_EN") (class "Default")
      (node (ref "R191") (pin "1") (pinfunction "1_1") (pintype "passive"))
      (node (ref "U1") (pin "P$35") (pinfunction "GPIO23_P$35") (pintype "bidirectional"))
    )
    (net (code "44") (name "GPIO24_TP_RST") (class "Default")
      (node (ref "FPC1") (pin "P$6") (pinfunction "YU/CTP_RST_P$6") (pintype "bidirectional"))
      (node (ref "P18") (pin "P$1") (pinfunction "P$1_P$1") (pintype "bidirectional"))
      (node (ref "U1") (pin "P$36") (pinfunction "GPIO24_P$36") (pintype "bidirectional"))
    )
    (net (code "45") (name "GPIO25_TP_INT") (class "Default")
      (node (ref "FPC1") (pin "P$5") (pinfunction "XL/CTP_INT_P$5") (pintype "bidirectional"))
      (node (ref "P17") (pin "P$1") (pinfunction "P$1_P$1") (pintype "bidirectional"))
      (node (ref "U1") (pin "P$37") (pinfunction "GPIO25_P$37") (pintype "bidirectional"))
    )
    (net (code "46") (name "IO_LED_VCC") (class "Default")
      (node (ref "C27") (pin "1") (pinfunction "1_1") (pintype "passive"))
      (node (ref "C28") (pin "1") (pinfunction "1_1") (pintype "passive"))
      (node (ref "C57") (pin "1") (pinfunction "1_1") (pintype "passive"))
      (node (ref "D012") (pin "1") (pinfunction "1_VDD_1") (pintype "bidirectional"))
      (node (ref "D019") (pin "1") (pinfunction "1_VDD_1") (pintype "bidirectional"))
      (node (ref "D021") (pin "1") (pinfunction "1_VDD_1") (pintype "bidirectional"))
      (node (ref "D022") (pin "1") (pinfunction "1_VDD_1") (pintype "bidirectional"))
      (node (ref "D023") (pin "1") (pinfunction "1_VDD_1") (pintype "bidirectional"))
      (node (ref "D024") (pin "1") (pinfunction "1_VDD_1") (pintype "bidirectional"))
      (node (ref "D025") (pin "1") (pinfunction "1_VDD_1") (pintype "bidirectional"))
      (node (ref "D026") (pin "1") (pinfunction "1_VDD_1") (pintype "bidirectional"))
      (node (ref "D027") (pin "1") (pinfunction "1_VDD_1") (pintype "bidirectional"))
      (node (ref "D028") (pin "1") (pinfunction "1_VDD_1") (pintype "bidirectional"))
      (node (ref "D029") (pin "1") (pinfunction "1_VDD_1") (pintype "bidirectional"))
      (node (ref "D030") (pin "1") (pinfunction "1_VDD_1") (pintype "bidirectional"))
      (node (ref "D031") (pin "1") (pinfunction "1_VDD_1") (pintype "bidirectional"))
      (node (ref "D032") (pin "1") (pinfunction "1_VDD_1") (pintype "bidirectional"))
      (node (ref "D033") (pin "1") (pinfunction "1_VDD_1") (pintype "bidirectional"))
      (node (ref "D183") (pin "1") (pinfunction "1_VDD_1") (pintype "bidirectional"))
      (node (ref "D184") (pin "1") (pinfunction "1_VDD_1") (pintype "bidirectional"))
      (node (ref "D185") (pin "1") (pinfunction "1_VDD_1") (pintype "bidirectional"))
      (node (ref "D186") (pin "1") (pinfunction "1_VDD_1") (pintype "bidirectional"))
      (node (ref "D187") (pin "1") (pinfunction "1_VDD_1") (pintype "bidirectional"))
      (node (ref "J110") (pin "1") (pinfunction "1_2B_1") (pintype "bidirectional"))
      (node (ref "U10") (pin "5") (pinfunction "VCC_5") (pintype "bidirectional"))
    )
    (net (code "47") (name "LED_K") (class "Default")
      (node (ref "FPC1") (pin "P$9") (pinfunction "BL_K_P$9") (pintype "bidirectional"))
      (node (ref "P14") (pin "P$1") (pinfunction "P$1_P$1") (pintype "bidirectional"))
      (node (ref "R40") (pin "2") (pinfunction "2_2") (pintype "passive"))
    )
    (net (code "48") (name "Net-(BUZ1-1+)") (class "Default")
      (node (ref "BUZ1") (pin "1") (pinfunction "1+_1") (pintype "bidirectional"))
      (node (ref "D004") (pin "-") (pinfunction "-_-") (pintype "passive"))
      (node (ref "R303") (pin "2") (pinfunction "2_2") (pintype "passive"))
    )
    (net (code "49") (name "Net-(BUZ1-2-)") (class "Default")
      (node (ref "BUZ1") (pin "2") (pinfunction "2-_2") (pintype "bidirectional"))
      (node (ref "D004") (pin "+") (pinfunction "+_+") (pintype "passive"))
      (node (ref "Q103") (pin "3") (pinfunction "C_3") (pintype "passive"))
    )
    (net (code "50") (name "Net-(C32-Pad2)") (class "Default")
      (node (ref "C32") (pin "2") (pinfunction "2_2") (pintype "passive"))
      (node (ref "J313") (pin "P$1") (pinfunction "P$1_P$1") (pintype "bidirectional"))
      (node (ref "R283") (pin "2") (pinfunction "2_2") (pintype "passive"))
    )
    (net (code "51") (name "Net-(D005-A)") (class "Default")
      (node (ref "D005") (pin "1") (pinfunction "A_1") (pintype "passive"))
      (node (ref "R20") (pin "2") (pinfunction "2_2") (pintype "passive"))
    )
    (net (code "52") (name "Net-(D005-C)") (class "Default")
      (node (ref "D005") (pin "2") (pinfunction "C_2") (pintype "passive"))
      (node (ref "Q2") (pin "3") (pinfunction "C_3") (pintype "passive"))
    )
    (net (code "53") (name "Net-(D006-A)") (class "Default")
      (node (ref "D006") (pin "1") (pinfunction "A_1") (pintype "passive"))
      (node (ref "R23") (pin "2") (pinfunction "2_2") (pintype "passive"))
    )
    (net (code "54") (name "Net-(D006-C)") (class "Default")
      (node (ref "D006") (pin "2") (pinfunction "C_2") (pintype "passive"))
      (node (ref "Q3") (pin "3") (pinfunction "C_3") (pintype "passive"))
    )
    (net (code "55") (name "Net-(D11-A)") (class "Default")
      (node (ref "D11") (pin "1") (pinfunction "A_1") (pintype "passive"))
      (node (ref "R7") (pin "2") (pinfunction "2_2") (pintype "passive"))
    )
    (net (code "56") (name "Net-(D11-C)") (class "Default")
      (node (ref "D11") (pin "2") (pinfunction "C_2") (pintype "passive"))
      (node (ref "Q1") (pin "3") (pinfunction "C_3") (pintype "passive"))
    )
    (net (code "57") (name "Net-(D012-2_DOUT)") (class "Default")
      (node (ref "D012") (pin "2") (pinfunction "2_DOUT_2") (pintype "bidirectional"))
      (node (ref "D019") (pin "4") (pinfunction "4_DIN_4") (pintype "bidirectional"))
    )
    (net (code "58") (name "Net-(D012-4_DIN)") (class "Default")
      (node (ref "D012") (pin "4") (pinfunction "4_DIN_4") (pintype "bidirectional"))
      (node (ref "D187") (pin "2") (pinfunction "2_DOUT_2") (pintype "bidirectional"))
    )
    (net (code "59") (name "Net-(D019-2_DOUT)") (class "Default")
      (node (ref "D019") (pin "2") (pinfunction "2_DOUT_2") (pintype "bidirectional"))
      (node (ref "D021") (pin "4") (pinfunction "4_DIN_4") (pintype "bidirectional"))
    )
    (net (code "60") (name "Net-(D021-2_DOUT)") (class "Default")
      (node (ref "D021") (pin "2") (pinfunction "2_DOUT_2") (pintype "bidirectional"))
      (node (ref "D022") (pin "4") (pinfunction "4_DIN_4") (pintype "bidirectional"))
    )
    (net (code "61") (name "Net-(D022-2_DOUT)") (class "Default")
      (node (ref "D022") (pin "2") (pinfunction "2_DOUT_2") (pintype "bidirectional"))
      (node (ref "D023") (pin "4") (pinfunction "4_DIN_4") (pintype "bidirectional"))
    )
    (net (code "62") (name "Net-(D023-2_DOUT)") (class "Default")
      (node (ref "D023") (pin "2") (pinfunction "2_DOUT_2") (pintype "bidirectional"))
      (node (ref "D024") (pin "4") (pinfunction "4_DIN_4") (pintype "bidirectional"))
    )
    (net (code "63") (name "Net-(D024-2_DOUT)") (class "Default")
      (node (ref "D024") (pin "2") (pinfunction "2_DOUT_2") (pintype "bidirectional"))
      (node (ref "D025") (pin "4") (pinfunction "4_DIN_4") (pintype "bidirectional"))
    )
    (net (code "64") (name "Net-(D025-2_DOUT)") (class "Default")
      (node (ref "D025") (pin "2") (pinfunction "2_DOUT_2") (pintype "bidirectional"))
      (node (ref "D026") (pin "4") (pinfunction "4_DIN_4") (pintype "bidirectional"))
    )
    (net (code "65") (name "Net-(D026-2_DOUT)") (class "Default")
      (node (ref "D026") (pin "2") (pinfunction "2_DOUT_2") (pintype "bidirectional"))
      (node (ref "D027") (pin "4") (pinfunction "4_DIN_4") (pintype "bidirectional"))
    )
    (net (code "66") (name "Net-(D027-2_DOUT)") (class "Default")
      (node (ref "D027") (pin "2") (pinfunction "2_DOUT_2") (pintype "bidirectional"))
      (node (ref "D028") (pin "4") (pinfunction "4_DIN_4") (pintype "bidirectional"))
    )
    (net (code "67") (name "Net-(D028-2_DOUT)") (class "Default")
      (node (ref "D028") (pin "2") (pinfunction "2_DOUT_2") (pintype "bidirectional"))
      (node (ref "D029") (pin "4") (pinfunction "4_DIN_4") (pintype "bidirectional"))
    )
    (net (code "68") (name "Net-(D029-2_DOUT)") (class "Default")
      (node (ref "D029") (pin "2") (pinfunction "2_DOUT_2") (pintype "bidirectional"))
      (node (ref "D030") (pin "4") (pinfunction "4_DIN_4") (pintype "bidirectional"))
    )
    (net (code "69") (name "Net-(D030-2_DOUT)") (class "Default")
      (node (ref "D030") (pin "2") (pinfunction "2_DOUT_2") (pintype "bidirectional"))
      (node (ref "D031") (pin "4") (pinfunction "4_DIN_4") (pintype "bidirectional"))
    )
    (net (code "70") (name "Net-(D031-2_DOUT)") (class "Default")
      (node (ref "D031") (pin "2") (pinfunction "2_DOUT_2") (pintype "bidirectional"))
      (node (ref "D032") (pin "4") (pinfunction "4_DIN_4") (pintype "bidirectional"))
    )
    (net (code "71") (name "Net-(D032-2_DOUT)") (class "Default")
      (node (ref "D032") (pin "2") (pinfunction "2_DOUT_2") (pintype "bidirectional"))
      (node (ref "D033") (pin "4") (pinfunction "4_DIN_4") (pintype "bidirectional"))
    )
    (net (code "72") (name "Net-(D143-2_K)") (class "Default")
      (node (ref "D143") (pin "2") (pinfunction "2_K_2") (pintype "passive"))
      (node (ref "R622") (pin "1") (pinfunction "1_1") (pintype "passive"))
    )
    (net (code "73") (name "Net-(D183-2_DOUT)") (class "Default")
      (node (ref "D183") (pin "2") (pinfunction "2_DOUT_2") (pintype "bidirectional"))
      (node (ref "D184") (pin "4") (pinfunction "4_DIN_4") (pintype "bidirectional"))
    )
    (net (code "74") (name "Net-(D184-2_DOUT)") (class "Default")
      (node (ref "D184") (pin "2") (pinfunction "2_DOUT_2") (pintype "bidirectional"))
      (node (ref "D185") (pin "4") (pinfunction "4_DIN_4") (pintype "bidirectional"))
    )
    (net (code "75") (name "Net-(D185-2_DOUT)") (class "Default")
      (node (ref "D185") (pin "2") (pinfunction "2_DOUT_2") (pintype "bidirectional"))
      (node (ref "D186") (pin "4") (pinfunction "4_DIN_4") (pintype "bidirectional"))
    )
    (net (code "76") (name "Net-(D186-2_DOUT)") (class "Default")
      (node (ref "D186") (pin "2") (pinfunction "2_DOUT_2") (pintype "bidirectional"))
      (node (ref "D187") (pin "4") (pinfunction "4_DIN_4") (pintype "bidirectional"))
    )
    (net (code "77") (name "Net-(J2-H-Pad5)") (class "Default")
      (node (ref "J2") (pin "5") (pinfunction "H_5") (pintype "bidirectional"))
      (node (ref "R35") (pin "2") (pinfunction "2_2") (pintype "passive"))
    )
    (net (code "78") (name "Net-(J3-+)") (class "Default")
      (node (ref "C65") (pin "2") (pinfunction "2_2") (pintype "passive"))
      (node (ref "C67") (pin "2") (pinfunction "2_2") (pintype "passive"))
      (node (ref "J3") (pin "1") (pinfunction "+_1") (pintype "bidirectional"))
      (node (ref "R56") (pin "1") (pinfunction "1_1") (pintype "passive"))
      (node (ref "R58") (pin "1") (pinfunction "1_1") (pintype "passive"))
    )
    (net (code "79") (name "Net-(J14-2_ECHO)") (class "Default")
      (node (ref "J14") (pin "P$2") (pinfunction "2_ECHO_P$2") (pintype "bidirectional"))
      (node (ref "R299") (pin "1") (pinfunction "1_1") (pintype "passive"))
    )
    (net (code "80") (name "Net-(J110-2_COM2)") (class "Default")
      (node (ref "C30") (pin "1") (pinfunction "1_1") (pintype "passive"))
      (node (ref "C90") (pin "1") (pinfunction "1_1") (pintype "passive"))
      (node (ref "J110") (pin "2") (pinfunction "2_COM2_2") (pintype "bidirectional"))
      (node (ref "J110") (pin "5") (pinfunction "5_COM1_5") (pintype "bidirectional"))
      (node (ref "P70") (pin "P$1") (pinfunction "P$1_P$1") (pintype "bidirectional"))
      (node (ref "R118") (pin "2") (pinfunction "2_2") (pintype "passive"))
      (node (ref "U34") (pin "1") (pinfunction "1_OUT_1") (pintype "bidirectional"))
    )
    (net (code "81") (name "Net-(K1-PadP$2)") (class "Default")
      (node (ref "K1") (pin "P$2") (pinfunction "P$2_P$2") (pintype "bidirectional"))
      (node (ref "R652") (pin "1") (pinfunction "1_1") (pintype "passive"))
    )
    (net (code "82") (name "Net-(K2-PadP$2)") (class "Default")
      (node (ref "K2") (pin "P$2") (pinfunction "P$2_P$2") (pintype "bidirectional"))
      (node (ref "R653") (pin "1") (pinfunction "1_1") (pintype "passive"))
    )
    (net (code "83") (name "Net-(K3-PadP$2)") (class "Default")
      (node (ref "K3") (pin "P$2") (pinfunction "P$2_P$2") (pintype "bidirectional"))
      (node (ref "R654") (pin "1") (pinfunction "1_1") (pintype "passive"))
    )
    (net (code "84") (name "Net-(K4-PadP$2)") (class "Default")
      (node (ref "K4") (pin "P$2") (pinfunction "P$2_P$2") (pintype "bidirectional"))
      (node (ref "R655") (pin "1") (pinfunction "1_1") (pintype "passive"))
    )
    (net (code "85") (name "Net-(L1-2)") (class "Default")
      (node (ref "L1") (pin "P$2") (pinfunction "2_P$2") (pintype "passive"))
      (node (ref "U1") (pin "P$48") (pinfunction "VREG_LX_P$48") (pintype "bidirectional"))
    )
    (net (code "86") (name "Net-(LED1-Pad+)") (class "Default")
      (node (ref "LED1") (pin "+") (pinfunction "+_+") (pintype "passive"))
      (node (ref "R24") (pin "1") (pinfunction "1_1") (pintype "passive"))
    )
    (net (code "87") (name "Net-(P101-P$1)") (class "Default")
      (node (ref "C212") (pin "2") (pinfunction "2_2") (pintype "passive"))
      (node (ref "P101") (pin "1") (pinfunction "P$1_1") (pintype "bidirectional"))
      (node (ref "U123") (pin "3") (pinfunction "IN_3") (pintype "bidirectional"))
    )
    (net (code "88") (name "Net-(Q1-B)") (class "Default")
      (node (ref "Q1") (pin "1") (pinfunction "B_1") (pintype "passive"))
      (node (ref "R4") (pin "2") (pinfunction "2_2") (pintype "passive"))
      (node (ref "R6") (pin "1") (pinfunction "1_1") (pintype "passive"))
    )
    (net (code "89") (name "Net-(Q2-B)") (class "Default")
      (node (ref "Q2") (pin "1") (pinfunction "B_1") (pintype "passive"))
      (node (ref "R13") (pin "2") (pinfunction "2_2") (pintype "passive"))
      (node (ref "R17") (pin "1") (pinfunction "1_1") (pintype "passive"))
    )
    (net (code "90") (name "Net-(Q3-B)") (class "Default")
      (node (ref "Q3") (pin "1") (pinfunction "B_1") (pintype "passive"))
      (node (ref "R21") (pin "2") (pinfunction "2_2") (pintype "passive"))
      (node (ref "R22") (pin "1") (pinfunction "1_1") (pintype "passive"))
    )
    (net (code "91") (name "Net-(Q5-B)") (class "Default")
      (node (ref "Q5") (pin "1") (pinfunction "B_1") (pintype "passive"))
      (node (ref "R41") (pin "1") (pinfunction "1_1") (pintype "passive"))
      (node (ref "R42") (pin "1") (pinfunction "1_1") (pintype "passive"))
    )
    (net (code "92") (name "Net-(Q5-C)") (class "Default")
      (node (ref "Q5") (pin "3") (pinfunction "C_3") (pintype "passive"))
      (node (ref "R40") (pin "1") (pinfunction "1_1") (pintype "passive"))
    )
    (net (code "93") (name "Net-(Q6-B)") (class "Default")
      (node (ref "C65") (pin "1") (pinfunction "1_1") (pintype "passive"))
      (node (ref "Q6") (pin "1") (pinfunction "B_1") (pintype "passive"))
      (node (ref "R57") (pin "1") (pinfunction "1_1") (pintype "passive"))
    )
    (net (code "94") (name "Net-(Q6-C)") (class "Default")
      (node (ref "C68") (pin "2") (pinfunction "2_2") (pintype "passive"))
      (node (ref "Q6") (pin "3") (pinfunction "C_3") (pintype "passive"))
      (node (ref "R59") (pin "1") (pinfunction "1_1") (pintype "passive"))
      (node (ref "U11") (pin "2") (pinfunction "2_IN1-_2") (pintype "bidirectional"))
    )
    (net (code "95") (name "Net-(Q103-B)") (class "Default")
      (node (ref "Q103") (pin "1") (pinfunction "B_1") (pintype "passive"))
      (node (ref "R284") (pin "2") (pinfunction "2_2") (pintype "passive"))
      (node (ref "R302") (pin "2") (pinfunction "2_2") (pintype "passive"))
    )
    (net (code "96") (name "Net-(Q104-B)") (class "Default")
      (node (ref "Q104") (pin "1") (pinfunction "B_1") (pintype "passive"))
      (node (ref "R282") (pin "2") (pinfunction "2_2") (pintype "passive"))
    )
    (net (code "97") (name "Net-(Q104-C)") (class "Default")
      (node (ref "J313") (pin "P$2") (pinfunction "P$2_P$2") (pintype "bidirectional"))
      (node (ref "Q104") (pin "3") (pinfunction "C_3") (pintype "passive"))
    )
    (net (code "98") (name "Net-(Q115-B)") (class "Default")
      (node (ref "Q115") (pin "1") (pinfunction "B_1") (pintype "passive"))
      (node (ref "R273") (pin "2") (pinfunction "2_2") (pintype "passive"))
      (node (ref "R274") (pin "1") (pinfunction "1_1") (pintype "passive"))
    )
    (net (code "99") (name "Net-(R25-Pad1)") (class "Default")
      (node (ref "R25") (pin "1") (pinfunction "1_1") (pintype "passive"))
      (node (ref "R280") (pin "2") (pinfunction "2_2") (pintype "passive"))
      (node (ref "R282") (pin "1") (pinfunction "1_1") (pintype "passive"))
    )
    (net (code "100") (name "Net-(R62-3)") (class "Default")
      (node (ref "R62") (pin "2") (pinfunction "3_2") (pintype "passive"))
      (node (ref "U11") (pin "3") (pinfunction "3_IN1+_3") (pintype "bidirectional"))
    )
    (net (code "101") (name "Net-(U1-GPIO2)") (class "Default")
      (node (ref "R26") (pin "1") (pinfunction "1_1") (pintype "passive"))
      (node (ref "U1") (pin "P$4") (pinfunction "GPIO2_P$4") (pintype "bidirectional"))
    )
    (net (code "102") (name "Net-(U1-GPIO3)") (class "Default")
      (node (ref "R27") (pin "1") (pinfunction "1_1") (pintype "passive"))
      (node (ref "U1") (pin "P$5") (pinfunction "GPIO3_P$5") (pintype "bidirectional"))
    )
    (net (code "103") (name "Net-(U1-GPIO4)") (class "Default")
      (node (ref "R28") (pin "1") (pinfunction "1_1") (pintype "passive"))
      (node (ref "U1") (pin "P$7") (pinfunction "GPIO4_P$7") (pintype "bidirectional"))
    )
    (net (code "104") (name "Net-(U1-GPIO5)") (class "Default")
      (node (ref "R29") (pin "1") (pinfunction "1_1") (pintype "passive"))
      (node (ref "U1") (pin "P$8") (pinfunction "GPIO5_P$8") (pintype "bidirectional"))
    )
    (net (code "105") (name "Net-(U1-VREG_AVDD)") (class "Default")
      (node (ref "C17") (pin "1") (pinfunction "1_1") (pintype "passive"))
      (node (ref "R16") (pin "2") (pinfunction "2_2") (pintype "passive"))
      (node (ref "U1") (pin "P$46") (pinfunction "VREG_AVDD_P$46") (pintype "bidirectional"))
    )
    (net (code "106") (name "Net-(U7-ADDR)") (class "Default")
      (node (ref "R12") (pin "1") (pinfunction "1_1") (pintype "passive"))
      (node (ref "R15") (pin "2") (pinfunction "2_2") (pintype "passive"))
      (node (ref "U7") (pin "2") (pinfunction "ADDR_2") (pintype "bidirectional"))
    )
    (net (code "107") (name "Net-(U7-DVI)") (class "Default")
      (node (ref "C3") (pin "2") (pinfunction "2_2") (pintype "passive"))
      (node (ref "R9") (pin "2") (pinfunction "2_2") (pintype "passive"))
      (node (ref "U7") (pin "5") (pinfunction "DVI_5") (pintype "bidirectional"))
    )
    (net (code "108") (name "Net-(U10-IN_A)") (class "Default")
      (node (ref "R54") (pin "2") (pinfunction "2_2") (pintype "passive"))
      (node (ref "U10") (pin "2") (pinfunction "IN_A_2") (pintype "bidirectional"))
    )
    (net (code "109") (name "Net-(U12-CPOUT)") (class "Default")
      (node (ref "C70") (pin "2") (pinfunction "2_2") (pintype "passive"))
      (node (ref "U12") (pin "20") (pinfunction "CPOUT_20") (pintype "bidirectional"))
    )
    (net (code "110") (name "Net-(U12-REGOUT)") (class "Default")
      (node (ref "C69") (pin "2") (pinfunction "2_2") (pintype "passive"))
      (node (ref "U12") (pin "10") (pinfunction "REGOUT_10") (pintype "bidirectional"))
    )
    (net (code "111") (name "Net-(U30-BF)") (class "Default")
      (node (ref "R3") (pin "2") (pinfunction "2_2") (pintype "passive"))
      (node (ref "R76") (pin "1") (pinfunction "1_1") (pintype "passive"))
      (node (ref "U30") (pin "3") (pinfunction "BF_3") (pintype "bidirectional"))
    )
    (net (code "112") (name "Net-(U30-BS)") (class "Default")
      (node (ref "C9") (pin "2") (pinfunction "2_2") (pintype "passive"))
      (node (ref "U30") (pin "1") (pinfunction "BS_1") (pintype "bidirectional"))
    )
    (net (code "113") (name "Net-(U30-EN)") (class "Default")
      (node (ref "R115") (pin "1") (pinfunction "1_1") (pintype "passive"))
      (node (ref "R191") (pin "2") (pinfunction "2_2") (pintype "passive"))
      (node (ref "U30") (pin "4") (pinfunction "EN_4") (pintype "bidirectional"))
    )
    (net (code "114") (name "Net-(U30-SW)") (class "Default")
      (node (ref "C9") (pin "1") (pinfunction "1_1") (pintype "passive"))
      (node (ref "L2") (pin "1") (pinfunction "1_1") (pintype "bidirectional"))
      (node (ref "U30") (pin "6") (pinfunction "SW_6") (pintype "bidirectional"))
    )
    (net (code "115") (name "Net-(U34-3_SET)") (class "Default")
      (node (ref "R117") (pin "1") (pinfunction "1_1") (pintype "passive"))
      (node (ref "U34") (pin "3") (pinfunction "3_SET_3") (pintype "bidirectional"))
    )
    (net (code "116") (name "Net-(U34-4_EN)") (class "Default")
      (node (ref "R116") (pin "1") (pinfunction "1_1") (pintype "passive"))
      (node (ref "U34") (pin "4") (pinfunction "4_EN_4") (pintype "bidirectional"))
    )
    (net (code "117") (name "Net-(U41-IADJ)") (class "Default")
      (node (ref "R190") (pin "1") (pinfunction "1_1") (pintype "passive"))
      (node (ref "U41") (pin "3") (pinfunction "IADJ_3") (pintype "bidirectional"))
    )
    (net (code "118") (name "Net-(U41-VOUT)") (class "Default")
      (node (ref "C44") (pin "1") (pinfunction "1_1") (pintype "passive"))
      (node (ref "FB1") (pin "2") (pinfunction "2_2") (pintype "passive"))
      (node (ref "FB2") (pin "1") (pinfunction "1_1") (pintype "passive"))
      (node (ref "U41") (pin "1") (pinfunction "VOUT_1") (pintype "bidirectional"))
    )
    (net (code "119") (name "Net-(U123-AHLB)") (class "Default")
      (node (ref "R288") (pin "1") (pinfunction "1_1") (pintype "passive"))
      (node (ref "U123") (pin "4") (pinfunction "AHLB_4") (pintype "bidirectional"))
      (node (ref "U123") (pin "6") (pinfunction "TOG_6") (pintype "bidirectional"))
    )
    (net (code "120") (name "Net-(U123-OUT)") (class "Default")
      (node (ref "R286") (pin "1") (pinfunction "1_1") (pintype "passive"))
      (node (ref "R287") (pin "1") (pinfunction "1_1") (pintype "passive"))
      (node (ref "U123") (pin "1") (pinfunction "OUT_1") (pintype "bidirectional"))
    )
    (net (code "121") (name "Net-(X1-XOUT)") (class "Default")
      (node (ref "C2") (pin "1") (pinfunction "1_1") (pintype "passive"))
      (node (ref "R8") (pin "2") (pinfunction "2_2") (pintype "passive"))
      (node (ref "X1") (pin "3") (pinfunction "XOUT_3") (pintype "bidirectional"))
    )
    (net (code "122") (name "QSPI_SCLK") (class "Default")
      (node (ref "U1") (pin "P$56") (pinfunction "QSPI_SCLK_P$56") (pintype "bidirectional"))
      (node (ref "U2") (pin "P$6") (pinfunction "SCLK_P$6") (pintype "bidirectional"))
      (node (ref "U3") (pin "6") (pinfunction "CLK_6") (pintype "bidirectional"))
    )
    (net (code "123") (name "QSPI_SD0") (class "Default")
      (node (ref "U1") (pin "P$57") (pinfunction "QSPI_SD0_P$57") (pintype "bidirectional"))
      (node (ref "U2") (pin "P$5") (pinfunction "SI/SIO0_P$5") (pintype "bidirectional"))
      (node (ref "U3") (pin "5") (pinfunction "DI(IO0)_5") (pintype "bidirectional"))
    )
    (net (code "124") (name "QSPI_SD1") (class "Default")
      (node (ref "U1") (pin "P$59") (pinfunction "QSPI_SD1_P$59") (pintype "bidirectional"))
      (node (ref "U2") (pin "P$2") (pinfunction "SO/SIO1_P$2") (pintype "bidirectional"))
      (node (ref "U3") (pin "2") (pinfunction "DO(IO1)_2") (pintype "bidirectional"))
    )
    (net (code "125") (name "QSPI_SD2") (class "Default")
      (node (ref "U1") (pin "P$58") (pinfunction "QSPI_SD2_P$58") (pintype "bidirectional"))
      (node (ref "U2") (pin "P$3") (pinfunction "SIO2_P$3") (pintype "bidirectional"))
      (node (ref "U3") (pin "3") (pinfunction "/WP(IO2)_3") (pintype "bidirectional"))
    )
    (net (code "126") (name "QSPI_SD3") (class "Default")
      (node (ref "U1") (pin "P$55") (pinfunction "QSPI_SD3_P$55") (pintype "bidirectional"))
      (node (ref "U2") (pin "P$7") (pinfunction "SIO3_P$7") (pintype "bidirectional"))
      (node (ref "U3") (pin "7") (pinfunction "/HOLD(IO3)_7") (pintype "bidirectional"))
    )
    (net (code "127") (name "QSPI_SS") (class "Default")
      (node (ref "R1") (pin "1") (pinfunction "1_1") (pintype "passive"))
      (node (ref "R2") (pin "1") (pinfunction "1_1") (pintype "passive"))
      (node (ref "U1") (pin "P$60") (pinfunction "QSPI_SS_P$60") (pintype "bidirectional"))
      (node (ref "U3") (pin "1") (pinfunction "/CS_1") (pintype "bidirectional"))
    )
    (net (code "128") (name "SWCLK") (class "Default")
      (node (ref "P5") (pin "P$1") (pinfunction "P$1_P$1") (pintype "bidirectional"))
      (node (ref "U1") (pin "P$24") (pinfunction "SWCLK_P$24") (pintype "bidirectional"))
    )
    (net (code "129") (name "SWDIO") (class "Default")
      (node (ref "P6") (pin "P$1") (pinfunction "P$1_P$1") (pintype "bidirectional"))
      (node (ref "U1") (pin "P$25") (pinfunction "SWD_P$25") (pintype "bidirectional"))
    )
    (net (code "130") (name "TFT_3V3") (class "Default")
      (node (ref "C47") (pin "2") (pinfunction "2_2") (pintype "passive"))
      (node (ref "C48") (pin "2") (pinfunction "2_2") (pintype "passive"))
      (node (ref "FB3") (pin "2") (pinfunction "2_2") (pintype "passive"))
      (node (ref "FPC1") (pin "P$10") (pinfunction "BL_A_P$10") (pintype "bidirectional"))
      (node (ref "FPC1") (pin "P$15") (pinfunction "VCC_P$15") (pintype "bidirectional"))
      (node (ref "FPC1") (pin "P$2") (pinfunction "VCC_P$2") (pintype "bidirectional"))
      (node (ref "P23") (pin "P$1") (pinfunction "P$1_P$1") (pintype "bidirectional"))
      (node (ref "R43") (pin "2") (pinfunction "2_2") (pintype "passive"))
      (node (ref "R44") (pin "2") (pinfunction "2_2") (pintype "passive"))
      (node (ref "R45") (pin "2") (pinfunction "2_2") (pintype "passive"))
      (node (ref "R46") (pin "2") (pinfunction "2_2") (pintype "passive"))
      (node (ref "R47") (pin "2") (pinfunction "2_2") (pintype "passive"))
    )
    (net (code "131") (name "TFT_RST") (class "Default")
      (node (ref "C49") (pin "2") (pinfunction "2_2") (pintype "passive"))
      (node (ref "D001") (pin "+") (pinfunction "+_+") (pintype "passive"))
      (node (ref "FPC1") (pin "P$11") (pinfunction "RESET_P$11") (pintype "bidirectional"))
      (node (ref "P13") (pin "P$1") (pinfunction "P$1_P$1") (pintype "bidirectional"))
      (node (ref "R47") (pin "1") (pinfunction "1_1") (pintype "passive"))
    )
    (net (code "132") (name "TYPE-C_N") (class "Default")
      (node (ref "J5") (pin "1") (pinfunction "1_1") (pintype "bidirectional"))
      (node (ref "J8") (pin "3") (pinfunction "3_3") (pintype "bidirectional"))
      (node (ref "R10") (pin "1") (pinfunction "1_1") (pintype "passive"))
    )
    (net (code "133") (name "TYPE-C_P") (class "Default")
      (node (ref "J6") (pin "1") (pinfunction "1_1") (pintype "bidirectional"))
      (node (ref "J8") (pin "2") (pinfunction "2_2") (pintype "bidirectional"))
      (node (ref "R11") (pin "1") (pinfunction "1_1") (pintype "passive"))
    )
    (net (code "134") (name "USB_D+") (class "Default")
      (node (ref "R11") (pin "2") (pinfunction "2_2") (pintype "passive"))
      (node (ref "U1") (pin "P$52") (pinfunction "USB_DP_P$52") (pintype "bidirectional"))
    )
    (net (code "135") (name "USB_D-") (class "Default")
      (node (ref "R10") (pin "2") (pinfunction "2_2") (pintype "passive"))
      (node (ref "U1") (pin "P$51") (pinfunction "USB_DM_P$51") (pintype "bidirectional"))
    )
    (net (code "136") (name "VBUS") (class "Default")
      (node (ref "C5") (pin "2") (pinfunction "2_2") (pintype "passive"))
      (node (ref "C51") (pin "1") (pinfunction "1_1") (pintype "passive"))
      (node (ref "FB1") (pin "1") (pinfunction "1_1") (pintype "passive"))
      (node (ref "J4") (pin "1") (pinfunction "1_1") (pintype "bidirectional"))
      (node (ref "J8") (pin "1") (pinfunction "1_1") (pintype "bidirectional"))
      (node (ref "U41") (pin "4") (pinfunction "EN_4") (pintype "bidirectional"))
      (node (ref "U41") (pin "5") (pinfunction "VIN_5") (pintype "bidirectional"))
    )
    (net (code "137") (name "VCC3V3") (class "Default")
      (node (ref "C29") (pin "1") (pinfunction "1_1") (pintype "passive"))
      (node (ref "C409") (pin "2") (pinfunction "2_2") (pintype "passive"))
      (node (ref "C412") (pin "2") (pinfunction "2_2") (pintype "passive"))
      (node (ref "C414") (pin "1") (pinfunction "1_1") (pintype "passive"))
      (node (ref "D143") (pin "1") (pinfunction "1_A_1") (pintype "passive"))
      (node (ref "FB4") (pin "1") (pinfunction "1_1") (pintype "passive"))
      (node (ref "L401") (pin "2") (pinfunction "2_2") (pintype "bidirectional"))
      (node (ref "P1") (pin "P$1") (pinfunction "P$1_P$1") (pintype "bidirectional"))
      (node (ref "P8") (pin "P$1") (pinfunction "P$1_P$1") (pintype "bidirectional"))
      (node (ref "R411") (pin "2") (pinfunction "2_2") (pintype "passive"))
    )
    (net (code "138") (name "VCC_3V3") (class "Default")
      (node (ref "C10") (pin "1") (pinfunction "1_1") (pintype "passive"))
      (node (ref "C11") (pin "1") (pinfunction "1_1") (pintype "passive"))
      (node (ref "C12") (pin "1") (pinfunction "1_1") (pintype "passive"))
      (node (ref "C13") (pin "1") (pinfunction "1_1") (pintype "passive"))
      (node (ref "C16") (pin "1") (pinfunction "1_1") (pintype "passive"))
      (node (ref "C20") (pin "1") (pinfunction "1_1") (pintype "passive"))
      (node (ref "C21") (pin "1") (pinfunction "1_1") (pintype "passive"))
      (node (ref "C213") (pin "2") (pinfunction "2_2") (pintype "passive"))
      (node (ref "C214") (pin "2") (pinfunction "2_2") (pintype "passive"))
      (node (ref "C22") (pin "1") (pinfunction "1_1") (pintype "passive"))
      (node (ref "C23") (pin "1") (pinfunction "1_1") (pintype "passive"))
      (node (ref "C25") (pin "2") (pinfunction "2_2") (pintype "passive"))
      (node (ref "C31") (pin "2") (pinfunction "2_2") (pintype "passive"))
      (node (ref "C37") (pin "2") (pinfunction "2_2") (pintype "passive"))
      (node (ref "C41") (pin "2") (pinfunction "2_2") (pintype "passive"))
      (node (ref "C42") (pin "2") (pinfunction "2_2") (pintype "passive"))
      (node (ref "C43") (pin "2") (pinfunction "2_2") (pintype "passive"))
      (node (ref "C45") (pin "2") (pinfunction "2_2") (pintype "passive"))
      (node (ref "C46") (pin "1") (pinfunction "1_1") (pintype "passive"))
      (node (ref "C50") (pin "2") (pinfunction "2_2") (pintype "passive"))
      (node (ref "C64") (pin "2") (pinfunction "2_2") (pintype "passive"))
      (node (ref "C7") (pin "2") (pinfunction "2_2") (pintype "passive"))
      (node (ref "C71") (pin "2") (pinfunction "2_2") (pintype "passive"))
      (node (ref "FB3") (pin "1") (pinfunction "1_1") (pintype "passive"))
      (node (ref "FB4") (pin "2") (pinfunction "2_2") (pintype "passive"))
      (node (ref "J14") (pin "P$4") (pinfunction "4VCC_P$4") (pintype "bidirectional"))
      (node (ref "P2") (pin "3") (pinfunction "2_3") (pintype "passive"))
      (node (ref "P3") (pin "P$1") (pinfunction "P$1_P$1") (pintype "bidirectional"))
      (node (ref "Q405") (pin "1") (pinfunction "G_1") (pintype "passive"))
      (node (ref "Q7") (pin "1") (pinfunction "G_1") (pintype "passive"))
      (node (ref "R1") (pin "2") (pinfunction "2_2") (pintype "passive"))
      (node (ref "R107") (pin "2") (pinfunction "2_2") (pintype "passive"))
      (node (ref "R12") (pin "2") (pinfunction "2_2") (pintype "passive"))
      (node (ref "R14") (pin "2") (pinfunction "2_2") (pintype "passive"))
      (node (ref "R16") (pin "1") (pinfunction "1_1") (pintype "passive"))
      (node (ref "R18") (pin "1") (pinfunction "1_1") (pintype "passive"))
      (node (ref "R19") (pin "1") (pinfunction "1_1") (pintype "passive"))
      (node (ref "R301") (pin "1") (pinfunction "1_1") (pintype "passive"))
      (node (ref "R422") (pin "2") (pinfunction "2_2") (pintype "passive"))
      (node (ref "R5") (pin "2") (pinfunction "2_2") (pintype "passive"))
      (node (ref "R57") (pin "2") (pinfunction "2_2") (pintype "passive"))
      (node (ref "R58") (pin "2") (pinfunction "2_2") (pintype "passive"))
      (node (ref "R59") (pin "2") (pinfunction "2_2") (pintype "passive"))
      (node (ref "R61") (pin "2") (pinfunction "2_2") (pintype "passive"))
      (node (ref "R62") (pin "3") (pinfunction "2_3") (pintype "passive"))
      (node (ref "R639") (pin "1") (pinfunction "1_1") (pintype "passive"))
      (node (ref "R9") (pin "1") (pinfunction "1_1") (pintype "passive"))
      (node (ref "U1") (pin "P$1") (pinfunction "IOVDD5_P$1") (pintype "power_in"))
      (node (ref "U1") (pin "P$11") (pinfunction "IOVDD4_P$11") (pintype "power_in"))
      (node (ref "U1") (pin "P$20") (pinfunction "IOVDD3_P$20") (pintype "power_in"))
      (node (ref "U1") (pin "P$30") (pinfunction "IOVDD2_P$30") (pintype "power_in"))
      (node (ref "U1") (pin "P$38") (pinfunction "IOVDD1_P$38") (pintype "power_in"))
      (node (ref "U1") (pin "P$44") (pinfunction "ADC_AVDD_P$44") (pintype "power_in"))
      (node (ref "U1") (pin "P$45") (pinfunction "IOVDD0_P$45") (pintype "power_in"))
      (node (ref "U1") (pin "P$49") (pinfunction "VREG_VIN_P$49") (pintype "bidirectional"))
      (node (ref "U1") (pin "P$53") (pinfunction "USB_OTP_VDD_P$53") (pintype "power_in"))
      (node (ref "U1") (pin "P$54") (pinfunction "QSPI_IOVDD_P$54") (pintype "power_in"))
      (node (ref "U11") (pin "8") (pinfunction "8_VCC_8") (pintype "bidirectional"))
      (node (ref "U12") (pin "13") (pinfunction "VDD_13") (pintype "bidirectional"))
      (node (ref "U12") (pin "8") (pinfunction "VLOGIC_8") (pintype "bidirectional"))
      (node (ref "U123") (pin "5") (pinfunction "VCC_5") (pintype "bidirectional"))
      (node (ref "U2") (pin "P$8") (pinfunction "VDD_P$8") (pintype "bidirectional"))
      (node (ref "U3") (pin "8") (pinfunction "VCC_8") (pintype "bidirectional"))
      (node (ref "U309") (pin "1") (pinfunction "P$1_1") (pintype "bidirectional"))
      (node (ref "U5") (pin "1") (pinfunction "VCC_1") (pintype "bidirectional"))
      (node (ref "U7") (pin "1") (pinfunction "VCC_1") (pintype "bidirectional"))
    )
    (net (code "139") (name "VCC_5V") (class "Default")
      (node (ref "C19") (pin "1") (pinfunction "1_1") (pintype "passive"))
      (node (ref "C33") (pin "2") (pinfunction "2_2") (pintype "passive"))
      (node (ref "C35") (pin "2") (pinfunction "2_2") (pintype "passive"))
      (node (ref "C38") (pin "2") (pinfunction "2_2") (pintype "passive"))
      (node (ref "C39") (pin "2") (pinfunction "2_2") (pintype "passive"))
      (node (ref "C411") (pin "2") (pinfunction "2_2") (pintype "passive"))
      (node (ref "C413") (pin "1") (pinfunction "1_1") (pintype "passive"))
      (node (ref "C6") (pin "2") (pinfunction "2_2") (pintype "passive"))
      (node (ref "C66") (pin "1") (pinfunction "1_1") (pintype "passive"))
      (node (ref "FB2") (pin "2") (pinfunction "2_2") (pintype "passive"))
      (node (ref "J1") (pin "3") (pinfunction "3_3") (pintype "bidirectional"))
      (node (ref "J2") (pin "2") (pinfunction "H_2") (pintype "bidirectional"))
      (node (ref "J2") (pin "3") (pinfunction "A_3") (pintype "bidirectional"))
      (node (ref "L11") (pin "1") (pinfunction "1_1") (pintype "bidirectional"))
      (node (ref "P10") (pin "P$1") (pinfunction "P$1_P$1") (pintype "bidirectional"))
      (node (ref "P7") (pin "P$1") (pinfunction "P$1_P$1") (pintype "bidirectional"))
      (node (ref "R20") (pin "1") (pinfunction "1_1") (pintype "passive"))
      (node (ref "R23") (pin "1") (pinfunction "1_1") (pintype "passive"))
      (node (ref "R283") (pin "1") (pinfunction "1_1") (pintype "passive"))
      (node (ref "R303") (pin "1") (pinfunction "1_1") (pintype "passive"))
      (node (ref "R423") (pin "1") (pinfunction "1_1") (pintype "passive"))
      (node (ref "R63") (pin "2") (pinfunction "2_2") (pintype "passive"))
      (node (ref "R7") (pin "1") (pinfunction "1_1") (pintype "passive"))
      (node (ref "U30") (pin "5") (pinfunction "IN_5") (pintype "bidirectional"))
      (node (ref "U401") (pin "P$1") (pinfunction "1_VIN_P$1") (pintype "bidirectional"))
      (node (ref "U6") (pin "1") (pinfunction "VCC_1") (pintype "power_in"))
    )
    (net (code "140") (name "VCC_IO_RGB") (class "Default")
      (node (ref "C183") (pin "1") (pinfunction "1_1") (pintype "passive"))
      (node (ref "C8") (pin "1") (pinfunction "1_1") (pintype "passive"))
      (node (ref "L2") (pin "2") (pinfunction "2_2") (pintype "bidirectional"))
      (node (ref "P69") (pin "P$1") (pinfunction "P$1_P$1") (pintype "bidirectional"))
      (node (ref "R116") (pin "2") (pinfunction "2_2") (pintype "passive"))
      (node (ref "R118") (pin "1") (pinfunction "1_1") (pintype "passive"))
      (node (ref "R76") (pin "2") (pinfunction "2_2") (pintype "passive"))
      (node (ref "U34") (pin "5") (pinfunction "5_VIN_5") (pintype "bidirectional"))
    )
    (net (code "141") (name "XIN") (class "Default")
      (node (ref "C1") (pin "2") (pinfunction "2_2") (pintype "passive"))
      (node (ref "U1") (pin "P$21") (pinfunction "XIN_P$21") (pintype "bidirectional"))
      (node (ref "X1") (pin "1") (pinfunction "XIN_1") (pintype "bidirectional"))
    )
    (net (code "142") (name "XOUT") (class "Default")
      (node (ref "R8") (pin "1") (pinfunction "1_1") (pintype "passive"))
      (node (ref "U1") (pin "P$22") (pinfunction "XOUT_P$22") (pintype "bidirectional"))
    )
    (net (code "143") (name "unconnected-(BOOT-2-PadP$2)") (class "Default")
      (node (ref "BOOT") (pin "P$2") (pinfunction "2_P$2") (pintype "bidirectional"))
    )
    (net (code "144") (name "unconnected-(BOOT-3-PadP$3)") (class "Default")
      (node (ref "BOOT") (pin "P$3") (pinfunction "3_P$3") (pintype "bidirectional"))
    )
    (net (code "145") (name "unconnected-(D033-2_DOUT-Pad2)") (class "Default")
      (node (ref "D033") (pin "2") (pinfunction "2_DOUT_2") (pintype "bidirectional"))
    )
    (net (code "146") (name "unconnected-(FPC1-NC-PadP$8)") (class "Default")
      (node (ref "FPC1") (pin "P$8") (pinfunction "NC_P$8") (pintype "bidirectional"))
    )
    (net (code "147") (name "unconnected-(J1-Pad2)") (class "Default")
      (node (ref "J1") (pin "2") (pinfunction "2_2") (pintype "bidirectional"))
    )
    (net (code "148") (name "unconnected-(J2-A-Pad1)") (class "Default")
      (node (ref "J2") (pin "1") (pinfunction "A_1") (pintype "bidirectional"))
    )
    (net (code "149") (name "unconnected-(J110-3_2A-Pad3)") (class "Default")
      (node (ref "J110") (pin "3") (pinfunction "3_2A_3") (pintype "bidirectional"))
    )
    (net (code "150") (name "unconnected-(J110-4_1A-Pad4)") (class "Default")
      (node (ref "J110") (pin "4") (pinfunction "4_1A_4") (pintype "bidirectional"))
    )
    (net (code "151") (name "unconnected-(J110-6_1B-Pad6)") (class "Default")
      (node (ref "J110") (pin "6") (pinfunction "6_1B_6") (pintype "bidirectional"))
    )
    (net (code "152") (name "unconnected-(RESET-1-PadP$1)") (class "Default")
      (node (ref "RESET") (pin "P$1") (pinfunction "1_P$1") (pintype "bidirectional"))
    )
    (net (code "153") (name "unconnected-(RESET-4-PadP$4)") (class "Default")
      (node (ref "RESET") (pin "P$4") (pinfunction "4_P$4") (pintype "bidirectional"))
    )
    (net (code "154") (name "unconnected-(U11-5_IN2+-Pad5)") (class "Default")
      (node (ref "U11") (pin "5") (pinfunction "5_IN2+_5") (pintype "bidirectional"))
    )
    (net (code "155") (name "unconnected-(U11-6_IN2--Pad6)") (class "Default")
      (node (ref "U11") (pin "6") (pinfunction "6_IN2-_6") (pintype "bidirectional"))
    )
    (net (code "156") (name "unconnected-(U11-7_OUT2-Pad7)") (class "Default")
      (node (ref "U11") (pin "7") (pinfunction "7_OUT2_7") (pintype "bidirectional"))
    )
    (net (code "157") (name "unconnected-(U12-AUX_CL-Pad7)") (class "Default")
      (node (ref "U12") (pin "7") (pinfunction "AUX_CL_7") (pintype "bidirectional"))
    )
    (net (code "158") (name "unconnected-(U12-AUX_DA-Pad6)") (class "Default")
      (node (ref "U12") (pin "6") (pinfunction "AUX_DA_6") (pintype "bidirectional"))
    )
    (net (code "159") (name "unconnected-(U12-INT-Pad12)") (class "Default")
      (node (ref "U12") (pin "12") (pinfunction "INT_12") (pintype "bidirectional"))
    )
  )
)
